# EEZ_DIB_AFE3_r1B3.net
KiCad netlist of a schematic drawn in EAGLE
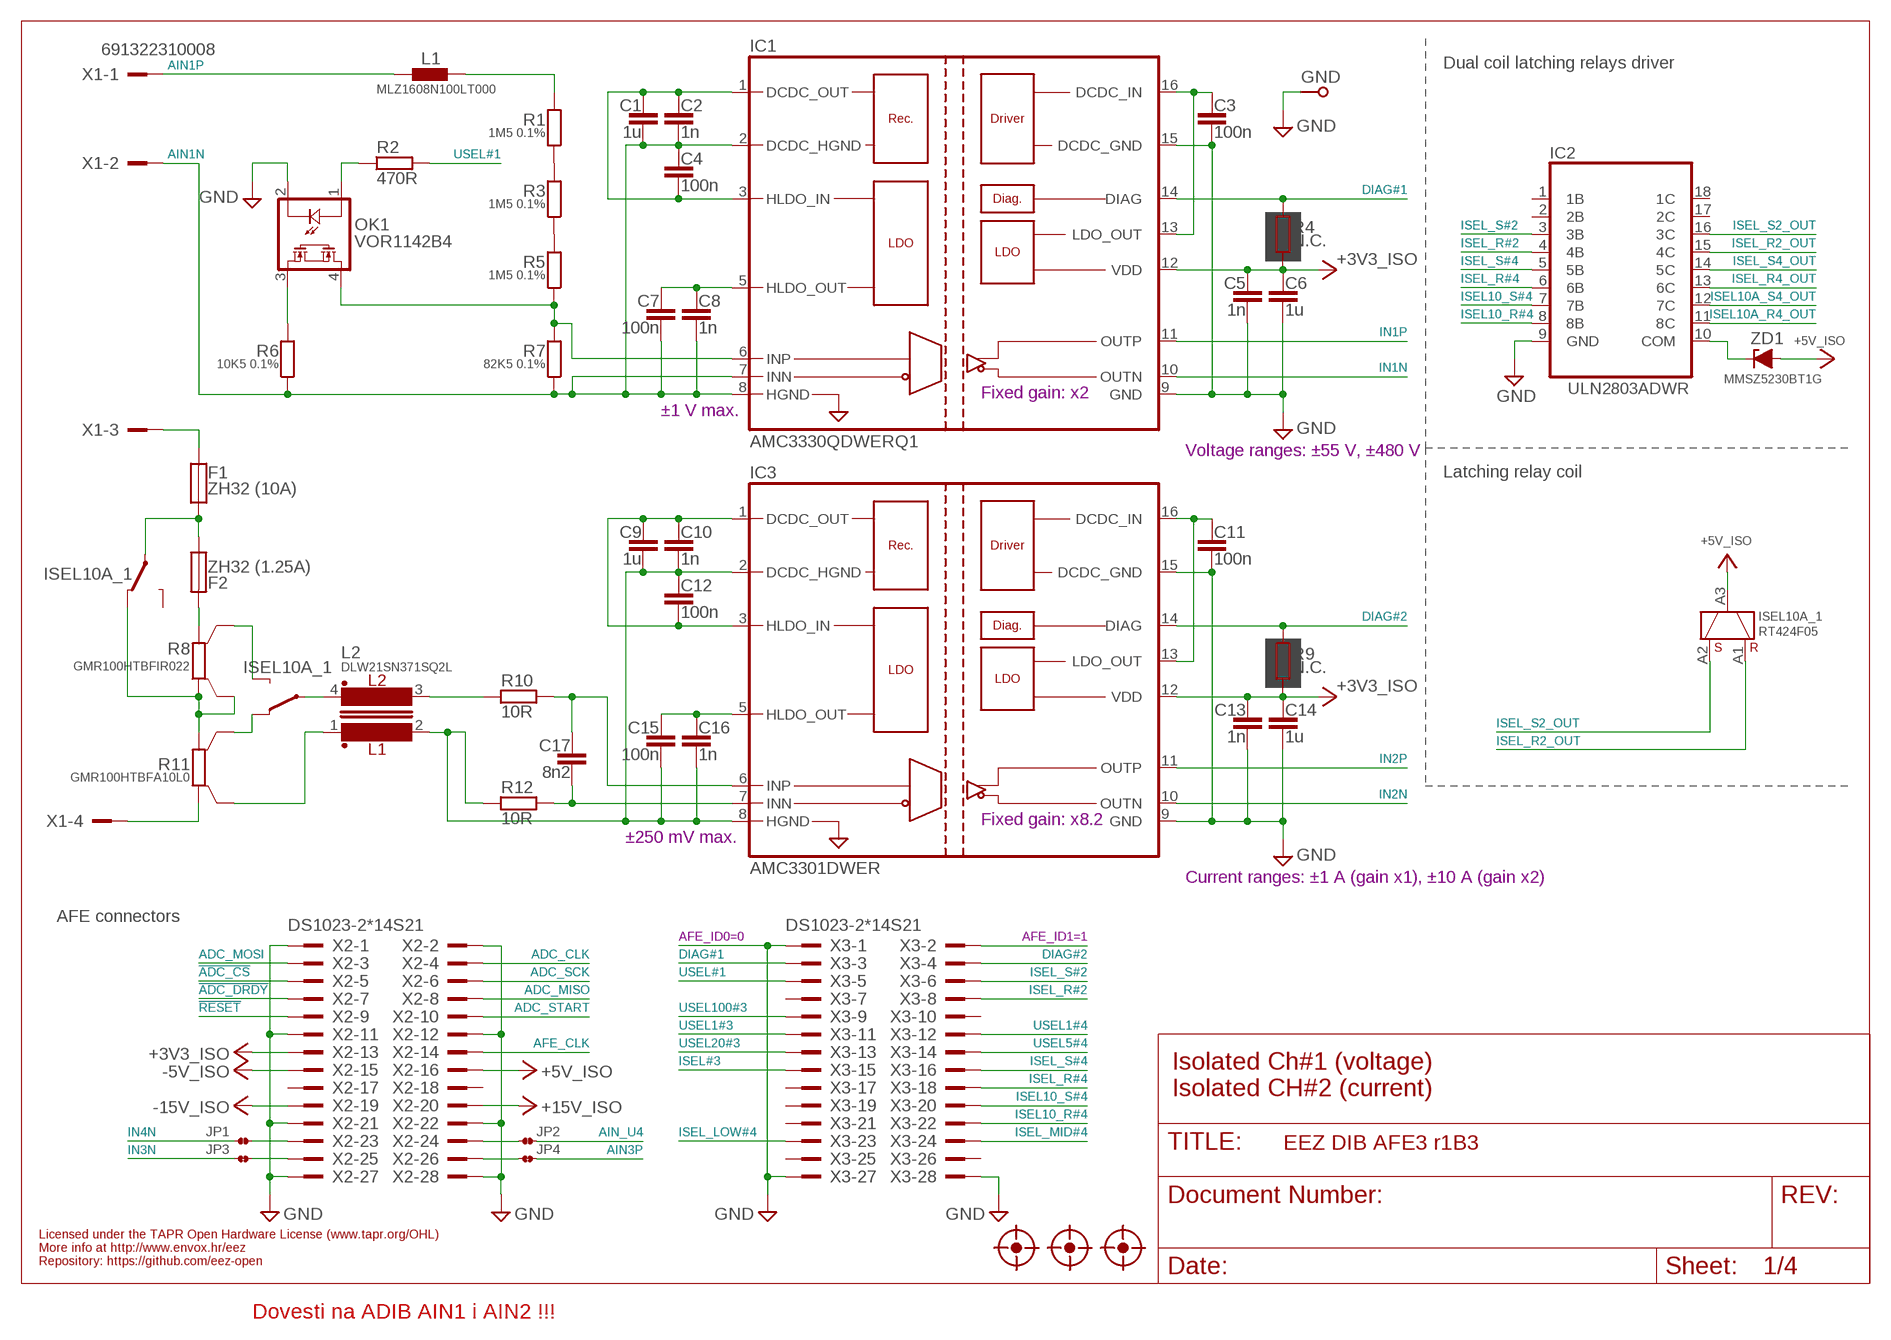
[diagram p0: schematic, sheet 1]
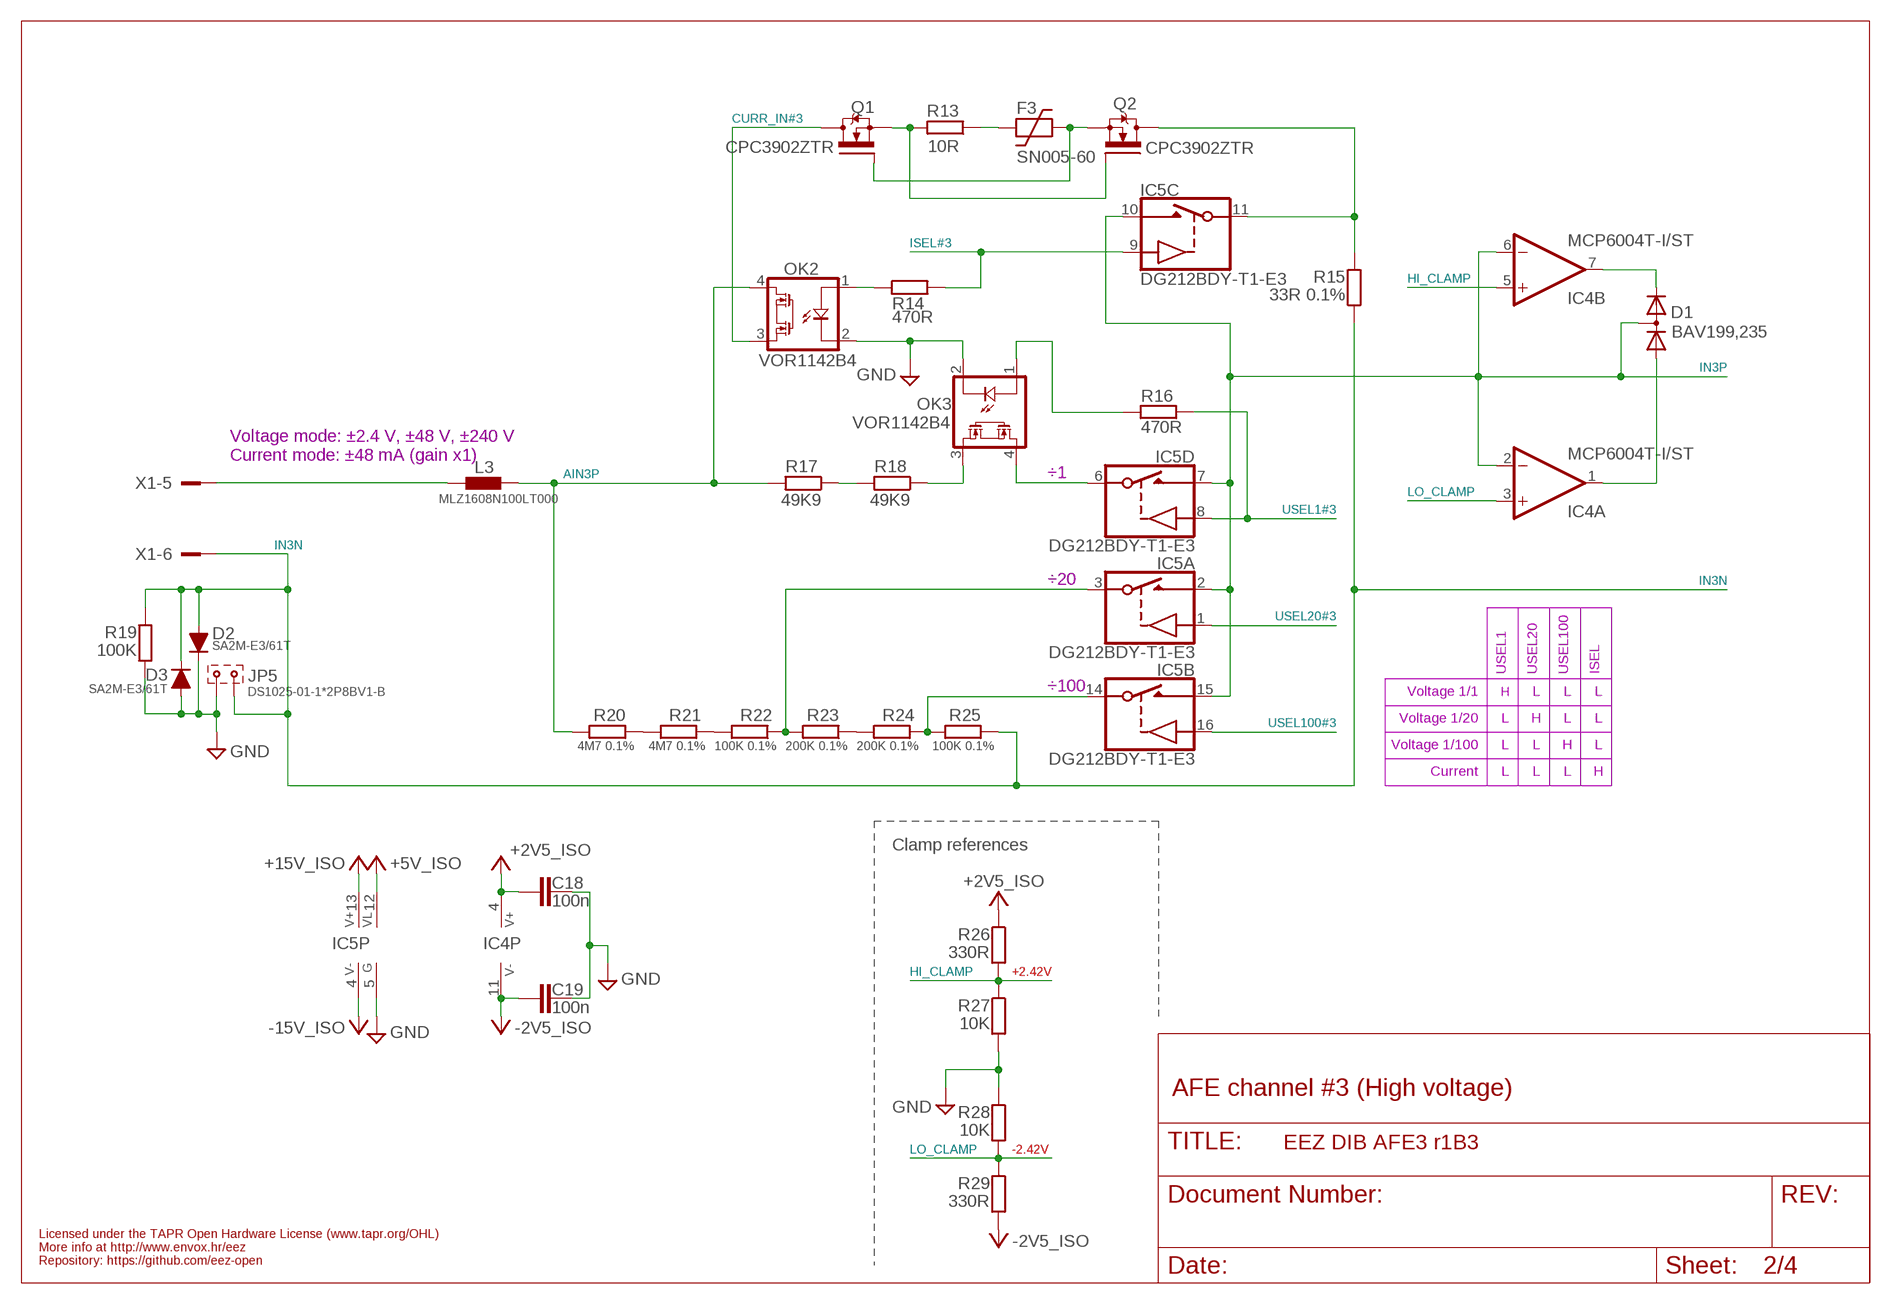
[diagram p1: schematic, sheet 2]
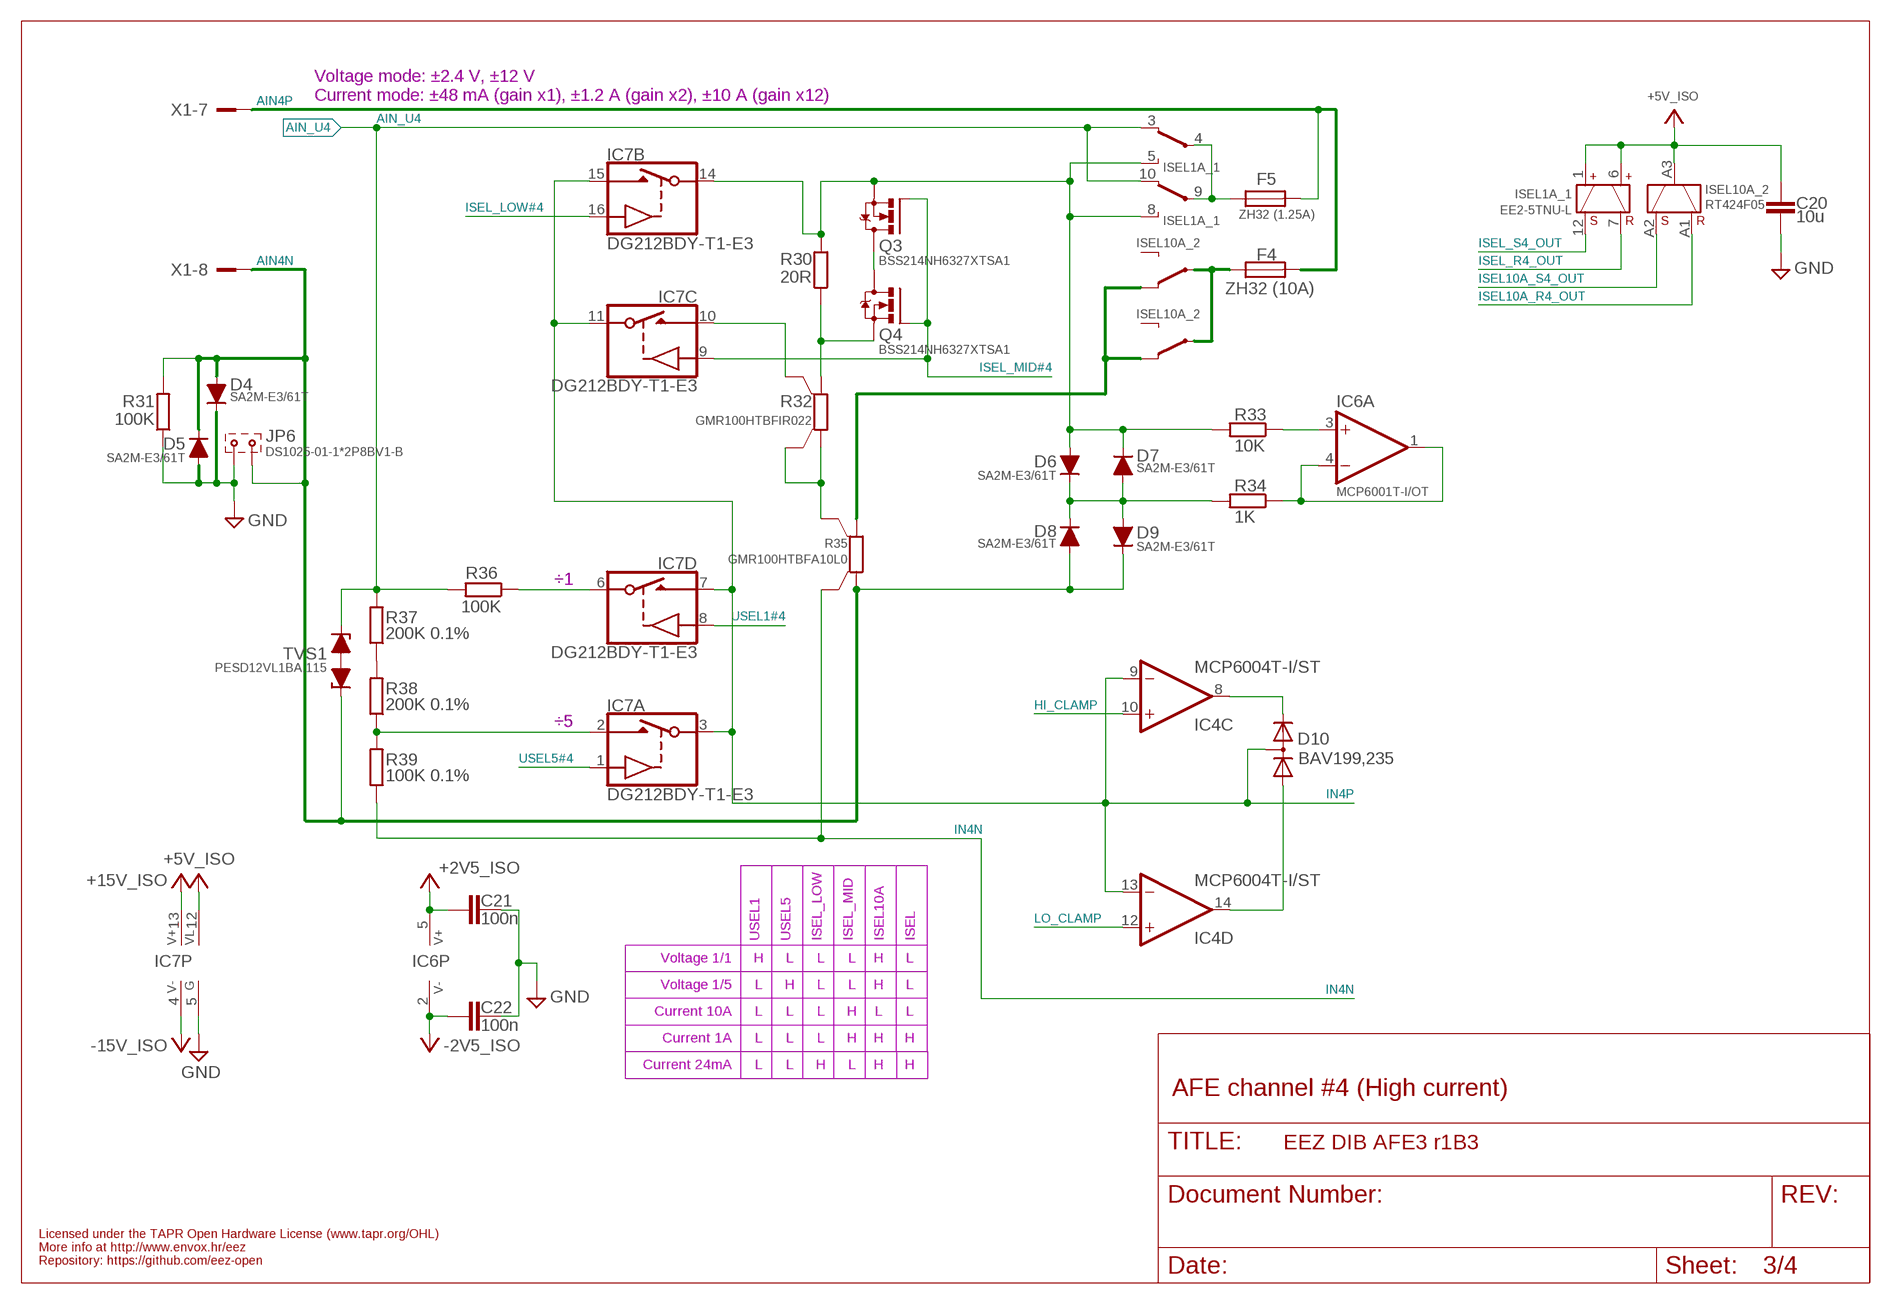
[diagram p2: schematic, sheet 3]
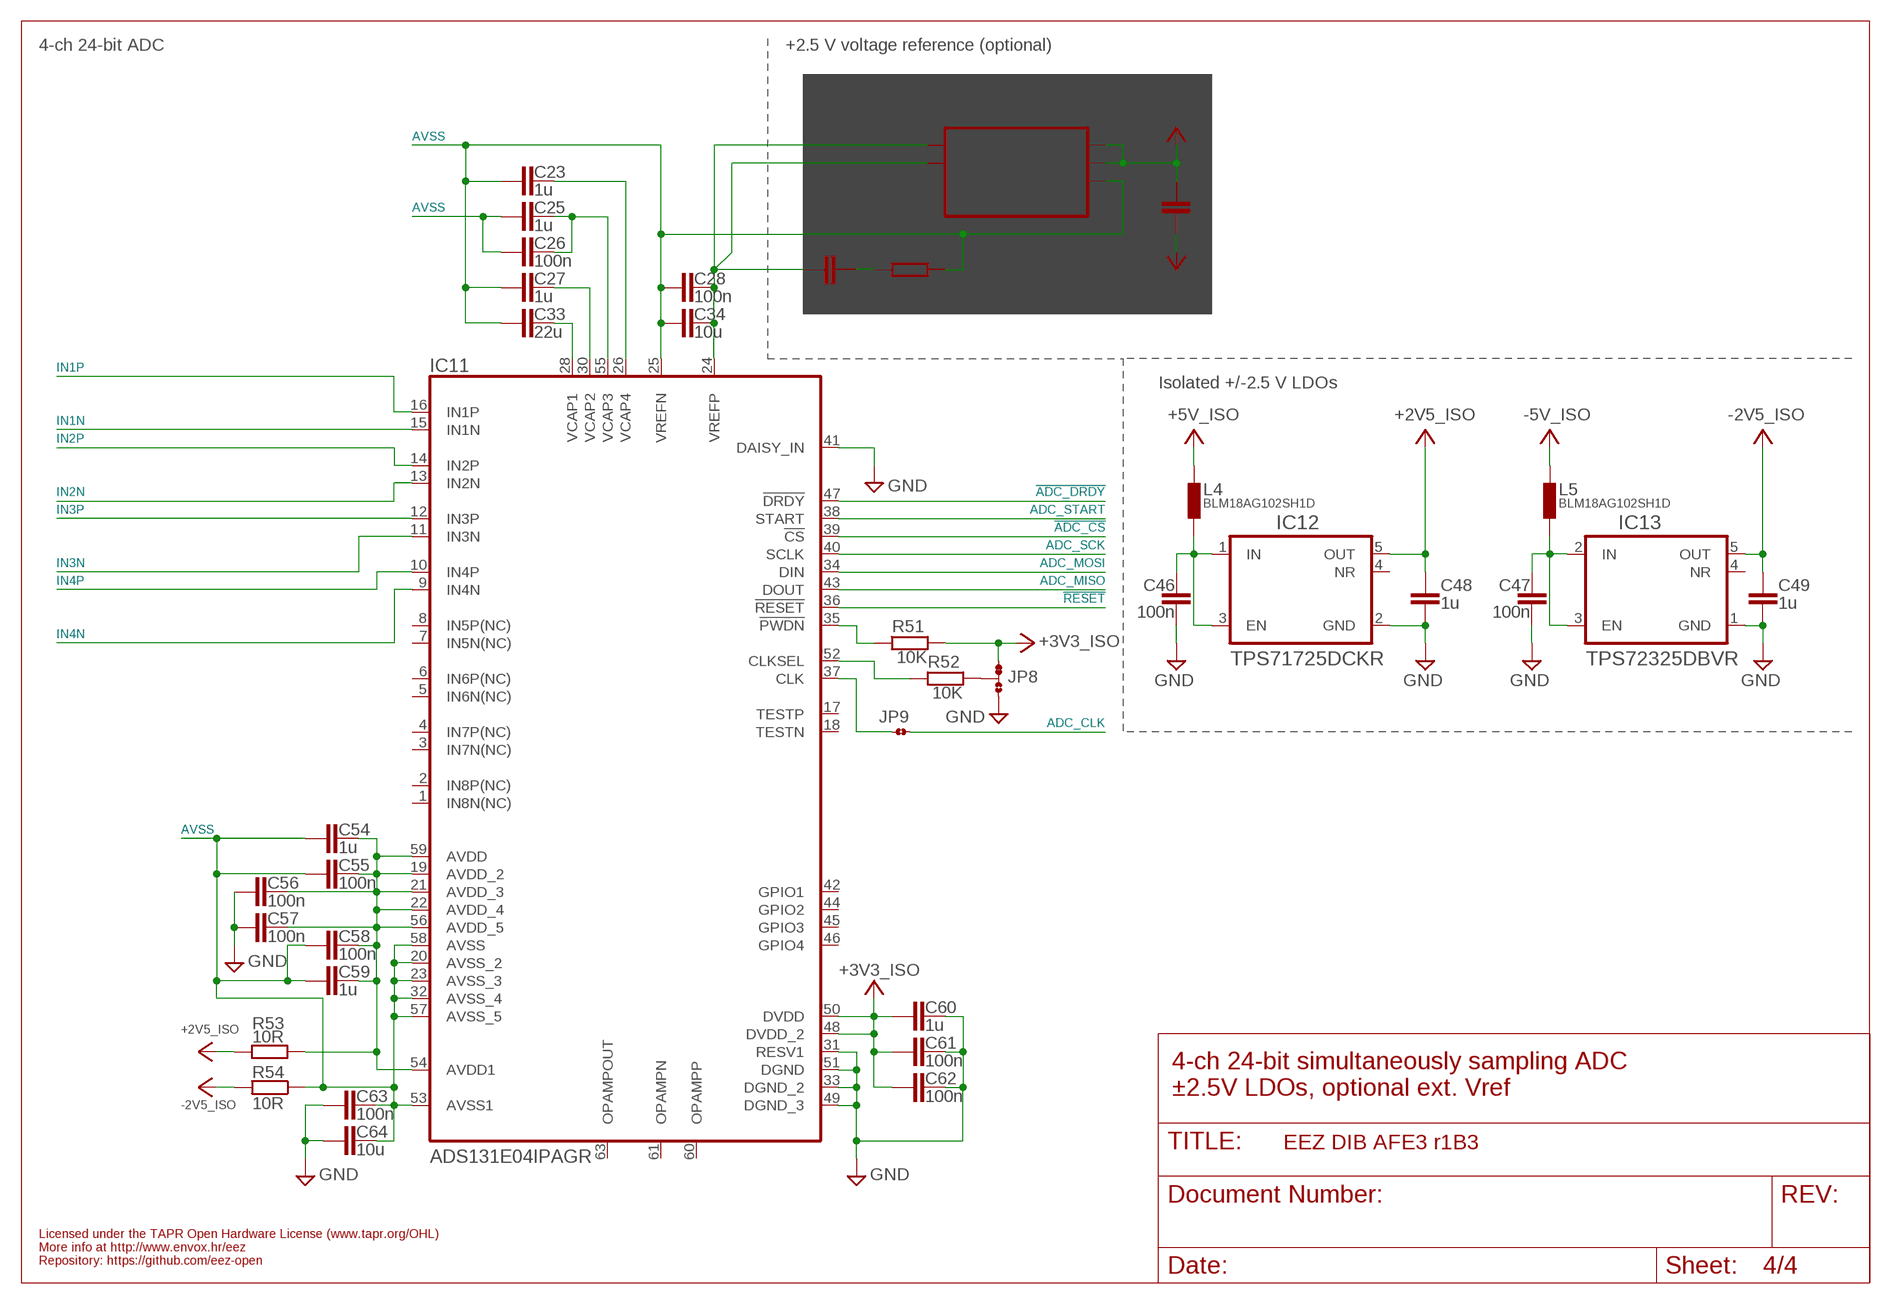
[diagram p3: schematic, sheet 4]

(export (version "E")
  (design (tool "Eeschema 10.0.6"))
  (components
    (comp (ref "C23")
      (value "1u")
      (footprint "eagle-import:C0805")
      (libsource (lib "eagle-import") (part "C-EUC0805"))
    )
    (comp (ref "C24")
      (value "N.C.")
      (footprint "eagle-import:C1206")
      (libsource (lib "eagle-import") (part "C-EUC1206"))
    )
    (comp (ref "C25")
      (value "1u")
      (footprint "eagle-import:C0805")
      (libsource (lib "eagle-import") (part "C-EUC0805"))
    )
    (comp (ref "C26")
      (value "100n")
      (footprint "eagle-import:C0603")
      (libsource (lib "eagle-import") (part "C-EUC0603"))
    )
    (comp (ref "C27")
      (value "1u")
      (footprint "eagle-import:C0805")
      (libsource (lib "eagle-import") (part "C-EUC0805"))
    )
    (comp (ref "C28")
      (value "100n")
      (footprint "eagle-import:C0603")
      (libsource (lib "eagle-import") (part "C-EUC0603"))
    )
    (comp (ref "C33")
      (value "22u")
      (footprint "eagle-import:C1206")
      (libsource (lib "eagle-import") (part "C-EUC1206"))
    )
    (comp (ref "C34")
      (value "10u")
      (footprint "eagle-import:C1206")
      (libsource (lib "eagle-import") (part "C-EUC1206"))
    )
    (comp (ref "C35")
      (value "N.C.")
      (footprint "eagle-import:C1206")
      (libsource (lib "eagle-import") (part "C-EUC1206"))
    )
    (comp (ref "C46")
      (value "100n")
      (footprint "eagle-import:C0603")
      (libsource (lib "eagle-import") (part "C-EUC0603"))
    )
    (comp (ref "C47")
      (value "100n")
      (footprint "eagle-import:C0603")
      (libsource (lib "eagle-import") (part "C-EUC0603"))
    )
    (comp (ref "C48")
      (value "1u")
      (footprint "eagle-import:C0805")
      (libsource (lib "eagle-import") (part "C-EUC0805"))
    )
    (comp (ref "C49")
      (value "1u")
      (footprint "eagle-import:C0805")
      (libsource (lib "eagle-import") (part "C-EUC0805"))
    )
    (comp (ref "C54")
      (value "1u")
      (footprint "eagle-import:C0805")
      (libsource (lib "eagle-import") (part "C-EUC0805"))
    )
    (comp (ref "C55")
      (value "100n")
      (footprint "eagle-import:C0603")
      (libsource (lib "eagle-import") (part "C-EUC0603"))
    )
    (comp (ref "C56")
      (value "100n")
      (footprint "eagle-import:C0603")
      (libsource (lib "eagle-import") (part "C-EUC0603"))
    )
    (comp (ref "C57")
      (value "100n")
      (footprint "eagle-import:C0603")
      (libsource (lib "eagle-import") (part "C-EUC0603"))
    )
    (comp (ref "C58")
      (value "100n")
      (footprint "eagle-import:C0603")
      (libsource (lib "eagle-import") (part "C-EUC0603"))
    )
    (comp (ref "C59")
      (value "1u")
      (footprint "eagle-import:C0805")
      (libsource (lib "eagle-import") (part "C-EUC0805"))
    )
    (comp (ref "C60")
      (value "1u")
      (footprint "eagle-import:C0805")
      (libsource (lib "eagle-import") (part "C-EUC0805"))
    )
    (comp (ref "C61")
      (value "100n")
      (footprint "eagle-import:C0603")
      (libsource (lib "eagle-import") (part "C-EUC0603"))
    )
    (comp (ref "C62")
      (value "100n")
      (footprint "eagle-import:C0603")
      (libsource (lib "eagle-import") (part "C-EUC0603"))
    )
    (comp (ref "C63")
      (value "100n")
      (footprint "eagle-import:C0603")
      (libsource (lib "eagle-import") (part "C-EUC0603"))
    )
    (comp (ref "C64")
      (value "10u")
      (footprint "eagle-import:C1206")
      (libsource (lib "eagle-import") (part "C-EUC1206"))
    )
    (comp (ref "IC8")
      (value "N.C.")
      (footprint "eagle-import:MSOP-8_MS_LIT")
      (libsource (lib "eagle-import") (part "LTC6655BHMS8"))
    )
    (comp (ref "IC11")
      (value "ADS131E04IPAGR")
      (footprint "eagle-import:PAG64")
      (libsource (lib "eagle-import") (part "ADS131E0XIPAG"))
    )
    (comp (ref "IC12")
      (value "TPS71725DCKR")
      (footprint "eagle-import:DCK5")
      (libsource (lib "eagle-import") (part "TPS71725DCKR"))
    )
    (comp (ref "IC13")
      (value "TPS72325DBVR")
      (footprint "eagle-import:DBV5")
      (libsource (lib "eagle-import") (part "TPS72325DBVR"))
    )
    (comp (ref "JP8")
      (value "JP3-CUT-0805-ROTATED")
      (footprint "eagle-import:JP3-0805-CUT2")
      (libsource (lib "eagle-import") (part "JP3-CUT-0805-ROTATED"))
    )
    (comp (ref "JP9")
      (value "JP2-CUT-0805")
      (footprint "eagle-import:R_0805")
      (libsource (lib "eagle-import") (part "JP2-CUT-0805"))
    )
    (comp (ref "L4")
      (value "BLM18AG102SH1D")
      (footprint "eagle-import:BEAD0603")
      (libsource (lib "eagle-import") (part "FERRITE_BEAD0603"))
    )
    (comp (ref "L5")
      (value "BLM18AG102SH1D")
      (footprint "eagle-import:BEAD0603")
      (libsource (lib "eagle-import") (part "FERRITE_BEAD0603"))
    )
    (comp (ref "R51")
      (value "10K")
      (footprint "eagle-import:R0805")
      (libsource (lib "eagle-import") (part "R-EU_R0805"))
    )
    (comp (ref "R52")
      (value "10K")
      (footprint "eagle-import:R0805")
      (libsource (lib "eagle-import") (part "R-EU_R0805"))
    )
    (comp (ref "R53")
      (value "10R")
      (footprint "eagle-import:R0805")
      (libsource (lib "eagle-import") (part "R-EU_R0805"))
    )
    (comp (ref "R54")
      (value "10R")
      (footprint "eagle-import:R0805")
      (libsource (lib "eagle-import") (part "R-EU_R0805"))
    )
    (comp (ref "R65")
      (value "N.C.")
      (footprint "eagle-import:R0805")
      (libsource (lib "eagle-import") (part "R-EU_R0805"))
    )
    (comp (ref "C18")
      (value "100n")
      (footprint "eagle-import:C0603")
      (libsource (lib "eagle-import") (part "C-EUC0603"))
    )
    (comp (ref "C19")
      (value "100n")
      (footprint "eagle-import:C0603")
      (libsource (lib "eagle-import") (part "C-EUC0603"))
    )
    (comp (ref "D1")
      (value "BAV199,235")
      (footprint "eagle-import:SOT23")
      (libsource (lib "eagle-import") (part "BAV199"))
    )
    (comp (ref "D2")
      (value "SA2M-E3/61T")
      (footprint "eagle-import:SMA_NARROW")
      (libsource (lib "eagle-import") (part "DIODE_SMA-NARROW"))
    )
    (comp (ref "D3")
      (value "SA2M-E3/61T")
      (footprint "eagle-import:SMA_NARROW")
      (libsource (lib "eagle-import") (part "DIODE_SMA-NARROW"))
    )
    (comp (ref "F3")
      (value "SN005-60")
      (footprint "eagle-import:C1206-HV")
      (libsource (lib "eagle-import") (part "FUSE_RESETTABLE2"))
    )
    (comp (ref "IC4")
      (value "MCP6004T-I/ST")
      (footprint "eagle-import:PW(R-PDSO-G14)")
      (libsource (lib "eagle-import") (part "OPA4197PW"))
    )
    (comp (ref "IC5")
      (value "DG212BDY-T1-E3")
      (footprint "eagle-import:SO16")
      (libsource (lib "eagle-import") (part "DG212BDY-T1-E3"))
    )
    (comp (ref "JP5")
      (value "DS1025-01-1*2P8BV1-B")
      (footprint "eagle-import:2MM-2")
      (libsource (lib "eagle-import") (part "JUMPER-2PIN-2MM"))
    )
    (comp (ref "L3")
      (value "MLZ1608N100LT000")
      (footprint "eagle-import:BEAD0603")
      (libsource (lib "eagle-import") (part "FERRITE_BEAD0603"))
    )
    (comp (ref "OK2")
      (value "VOR1142B4")
      (footprint "eagle-import:DIL4-SMD")
      (libsource (lib "eagle-import") (part "VOR1142B4"))
    )
    (comp (ref "OK3")
      (value "VOR1142B4")
      (footprint "eagle-import:DIL4-SMD")
      (libsource (lib "eagle-import") (part "VOR1142B4"))
    )
    (comp (ref "Q1")
      (value "CPC3902ZTR")
      (footprint "eagle-import:SOT230P700X180-4N")
      (libsource (lib "eagle-import") (part "BSP129SOT-223"))
    )
    (comp (ref "Q2")
      (value "CPC3902ZTR")
      (footprint "eagle-import:SOT230P700X180-4N")
      (libsource (lib "eagle-import") (part "BSP129SOT-223"))
    )
    (comp (ref "R13")
      (value "10R")
      (footprint "eagle-import:R0805")
      (libsource (lib "eagle-import") (part "R-EU_R0805"))
    )
    (comp (ref "R14")
      (value "470R")
      (footprint "eagle-import:R0805")
      (libsource (lib "eagle-import") (part "R-EU_R0805"))
    )
    (comp (ref "R15")
      (value "33R 0.1%")
      (footprint "eagle-import:R1206")
      (libsource (lib "eagle-import") (part "R-EU_R1206"))
    )
    (comp (ref "R16")
      (value "470R")
      (footprint "eagle-import:R0805")
      (libsource (lib "eagle-import") (part "R-EU_R0805"))
    )
    (comp (ref "R17")
      (value "49K9")
      (footprint "eagle-import:R1206")
      (libsource (lib "eagle-import") (part "R-EU_R1206"))
    )
    (comp (ref "R18")
      (value "49K9")
      (footprint "eagle-import:R1206")
      (libsource (lib "eagle-import") (part "R-EU_R1206"))
    )
    (comp (ref "R19")
      (value "100K")
      (footprint "eagle-import:R1206")
      (libsource (lib "eagle-import") (part "R-EU_R1206"))
    )
    (comp (ref "R20")
      (value "4M7 0.1%")
      (footprint "eagle-import:R1206")
      (libsource (lib "eagle-import") (part "R-EU_R1206"))
    )
    (comp (ref "R21")
      (value "4M7 0.1%")
      (footprint "eagle-import:R1206")
      (libsource (lib "eagle-import") (part "R-EU_R1206"))
    )
    (comp (ref "R22")
      (value "100K 0.1%")
      (footprint "eagle-import:R1206")
      (libsource (lib "eagle-import") (part "R-EU_R1206"))
    )
    (comp (ref "R23")
      (value "200K 0.1%")
      (footprint "eagle-import:R1206")
      (libsource (lib "eagle-import") (part "R-EU_R1206"))
    )
    (comp (ref "R24")
      (value "200K 0.1%")
      (footprint "eagle-import:R1206")
      (libsource (lib "eagle-import") (part "R-EU_R1206"))
    )
    (comp (ref "R25")
      (value "100K 0.1%")
      (footprint "eagle-import:R1206")
      (libsource (lib "eagle-import") (part "R-EU_R1206"))
    )
    (comp (ref "R26")
      (value "330R")
      (footprint "eagle-import:R0805")
      (libsource (lib "eagle-import") (part "R-EU_R0805"))
    )
    (comp (ref "R27")
      (value "10K")
      (footprint "eagle-import:R0805")
      (libsource (lib "eagle-import") (part "R-EU_R0805"))
    )
    (comp (ref "R28")
      (value "10K")
      (footprint "eagle-import:R0805")
      (libsource (lib "eagle-import") (part "R-EU_R0805"))
    )
    (comp (ref "R29")
      (value "330R")
      (footprint "eagle-import:R0805")
      (libsource (lib "eagle-import") (part "R-EU_R0805"))
    )
    (comp (ref "X1")
      (value "691322310008")
      (footprint "eagle-import:691322310008")
      (libsource (lib "eagle-import") (part "691322310008"))
    )
    (comp (ref "C20")
      (value "10u")
      (footprint "eagle-import:C1206")
      (libsource (lib "eagle-import") (part "C-EUC1206"))
    )
    (comp (ref "C21")
      (value "100n")
      (footprint "eagle-import:C0603")
      (libsource (lib "eagle-import") (part "C-EUC0603"))
    )
    (comp (ref "C22")
      (value "100n")
      (footprint "eagle-import:C0603")
      (libsource (lib "eagle-import") (part "C-EUC0603"))
    )
    (comp (ref "D4")
      (value "SA2M-E3/61T")
      (footprint "eagle-import:SMA_NARROW")
      (libsource (lib "eagle-import") (part "DIODE_SMA-NARROW"))
    )
    (comp (ref "D5")
      (value "SA2M-E3/61T")
      (footprint "eagle-import:SMA_NARROW")
      (libsource (lib "eagle-import") (part "DIODE_SMA-NARROW"))
    )
    (comp (ref "D6")
      (value "SA2M-E3/61T")
      (footprint "eagle-import:SMA_NARROW")
      (libsource (lib "eagle-import") (part "DIODE_SMA-NARROW"))
    )
    (comp (ref "D7")
      (value "SA2M-E3/61T")
      (footprint "eagle-import:SMA_NARROW")
      (libsource (lib "eagle-import") (part "DIODE_SMA-NARROW"))
    )
    (comp (ref "D8")
      (value "SA2M-E3/61T")
      (footprint "eagle-import:SMA_NARROW")
      (libsource (lib "eagle-import") (part "DIODE_SMA-NARROW"))
    )
    (comp (ref "D9")
      (value "SA2M-E3/61T")
      (footprint "eagle-import:SMA_NARROW")
      (libsource (lib "eagle-import") (part "DIODE_SMA-NARROW"))
    )
    (comp (ref "D10")
      (value "BAV199,235")
      (footprint "eagle-import:SOT23")
      (libsource (lib "eagle-import") (part "BAV199"))
    )
    (comp (ref "F4")
      (value "ZH32 (10A)")
      (footprint "eagle-import:ZH32")
      (libsource (lib "eagle-import") (part "ZH32"))
    )
    (comp (ref "F5")
      (value "ZH32 (1.25A)")
      (footprint "eagle-import:ZH32")
      (libsource (lib "eagle-import") (part "ZH32"))
    )
    (comp (ref "IC6")
      (value "MCP6001T-I/OT")
      (footprint "eagle-import:DBV5")
      (libsource (lib "eagle-import") (part "OPA376AIDBVR"))
    )
    (comp (ref "IC7")
      (value "DG212BDY-T1-E3")
      (footprint "eagle-import:SO16")
      (libsource (lib "eagle-import") (part "DG212BDY-T1-E3"))
    )
    (comp (ref "ISEL1A_1")
      (value "EE2-5TNU-L")
      (footprint "eagle-import:G6SK-2F")
      (libsource (lib "eagle-import") (part "G6SK-2F"))
    )
    (comp (ref "ISEL10A_2")
      (value "RT424F05")
      (footprint "eagle-import:RT424FXX")
      (libsource (lib "eagle-import") (part "RT424FXX"))
    )
    (comp (ref "JP6")
      (value "DS1025-01-1*2P8BV1-B")
      (footprint "eagle-import:2MM-2")
      (libsource (lib "eagle-import") (part "JUMPER-2PIN-2MM"))
    )
    (comp (ref "Q3")
      (value "BSS214NH6327XTSA1")
      (footprint "eagle-import:SOT103P240X110-3N")
      (fields
        (field (name "MPN") "2N7002-7-F")
        (field (name "MPN_1") "2N7002-7-F")
        (field (name "OC_FARNELL") "1713823")
        (field (name "OC_NEWARK") "25R5679")
        (field (name "PACKAGE") "SOT-23-3")
        (field (name "SUPPLIER") "DIODES INC.")
      )
      (libsource (lib "eagle-import") (part "2N7002"))
    )
    (comp (ref "Q4")
      (value "BSS214NH6327XTSA1")
      (footprint "eagle-import:SOT103P240X110-3N")
      (fields (field (name "MPN") "2N7002-7-F"))
      (libsource (lib "eagle-import") (part "2N7002"))
    )
    (comp (ref "R30")
      (value "20R")
      (footprint "eagle-import:R1206")
      (libsource (lib "eagle-import") (part "R-EU_R1206"))
    )
    (comp (ref "R31")
      (value "100K")
      (footprint "eagle-import:R1206")
      (libsource (lib "eagle-import") (part "R-EU_R1206"))
    )
    (comp (ref "R32")
      (value "GMR100HTBFIR022")
      (footprint "eagle-import:R_2512-4WIRE")
      (libsource (lib "eagle-import") (part "R-EU_4WIRE2512"))
    )
    (comp (ref "R33")
      (value "10K")
      (footprint "eagle-import:R0805")
      (libsource (lib "eagle-import") (part "R-EU_R0805"))
    )
    (comp (ref "R34")
      (value "1K")
      (footprint "eagle-import:R0805")
      (libsource (lib "eagle-import") (part "R-EU_R0805"))
    )
    (comp (ref "R35")
      (value "GMR100HTBFA10L0")
      (footprint "eagle-import:R_2512-4WIRE")
      (libsource (lib "eagle-import") (part "R-EU_4WIRE2512"))
    )
    (comp (ref "R36")
      (value "100K")
      (footprint "eagle-import:R1206")
      (libsource (lib "eagle-import") (part "R-EU_R1206"))
    )
    (comp (ref "R37")
      (value "200K 0.1%")
      (footprint "eagle-import:R1206")
      (libsource (lib "eagle-import") (part "R-EU_R1206"))
    )
    (comp (ref "R38")
      (value "200K 0.1%")
      (footprint "eagle-import:R1206")
      (libsource (lib "eagle-import") (part "R-EU_R1206"))
    )
    (comp (ref "R39")
      (value "100K 0.1%")
      (footprint "eagle-import:R1206")
      (libsource (lib "eagle-import") (part "R-EU_R1206"))
    )
    (comp (ref "TVS1")
      (value "PESD12VL1BA,115")
      (footprint "eagle-import:SOD323-BIDIR")
      (libsource (lib "eagle-import") (part "PESDXL1BA"))
    )
    (comp (ref "C1")
      (value "1u")
      (footprint "eagle-import:C0603")
      (libsource (lib "eagle-import") (part "C-EUC0603"))
    )
    (comp (ref "C2")
      (value "1n")
      (footprint "eagle-import:C0603")
      (libsource (lib "eagle-import") (part "C-EUC0603"))
    )
    (comp (ref "C3")
      (value "100n")
      (footprint "eagle-import:C0603")
      (libsource (lib "eagle-import") (part "C-EUC0603"))
    )
    (comp (ref "C4")
      (value "100n")
      (footprint "eagle-import:C0603")
      (libsource (lib "eagle-import") (part "C-EUC0603"))
    )
    (comp (ref "C5")
      (value "1n")
      (footprint "eagle-import:C1206")
      (libsource (lib "eagle-import") (part "C-EUC1206"))
    )
    (comp (ref "C6")
      (value "1u")
      (footprint "eagle-import:C1206")
      (libsource (lib "eagle-import") (part "C-EUC1206"))
    )
    (comp (ref "C7")
      (value "100n")
      (footprint "eagle-import:C1206")
      (libsource (lib "eagle-import") (part "C-EUC1206"))
    )
    (comp (ref "C8")
      (value "1n")
      (footprint "eagle-import:C1206")
      (libsource (lib "eagle-import") (part "C-EUC1206"))
    )
    (comp (ref "C9")
      (value "1u")
      (footprint "eagle-import:C0603")
      (libsource (lib "eagle-import") (part "C-EUC0603"))
    )
    (comp (ref "C10")
      (value "1n")
      (footprint "eagle-import:C0603")
      (libsource (lib "eagle-import") (part "C-EUC0603"))
    )
    (comp (ref "C11")
      (value "100n")
      (footprint "eagle-import:C0603")
      (libsource (lib "eagle-import") (part "C-EUC0603"))
    )
    (comp (ref "C12")
      (value "100n")
      (footprint "eagle-import:C0603")
      (libsource (lib "eagle-import") (part "C-EUC0603"))
    )
    (comp (ref "C13")
      (value "1n")
      (footprint "eagle-import:C1206")
      (libsource (lib "eagle-import") (part "C-EUC1206"))
    )
    (comp (ref "C14")
      (value "1u")
      (footprint "eagle-import:C1206")
      (libsource (lib "eagle-import") (part "C-EUC1206"))
    )
    (comp (ref "C15")
      (value "100n")
      (footprint "eagle-import:C1206")
      (libsource (lib "eagle-import") (part "C-EUC1206"))
    )
    (comp (ref "C16")
      (value "1n")
      (footprint "eagle-import:C1206")
      (libsource (lib "eagle-import") (part "C-EUC1206"))
    )
    (comp (ref "C17")
      (value "8n2")
      (footprint "eagle-import:C0603")
      (libsource (lib "eagle-import") (part "C-EUC0603"))
    )
    (comp (ref "F1")
      (value "ZH32 (10A)")
      (footprint "eagle-import:ZH32")
      (libsource (lib "eagle-import") (part "ZH32"))
    )
    (comp (ref "F2")
      (value "ZH32 (1.25A)")
      (footprint "eagle-import:ZH32")
      (libsource (lib "eagle-import") (part "ZH32"))
    )
    (comp (ref "FM1")
      (value "FIDUCIAL_2")
      (footprint "eagle-import:FIDUCIAL_DUAL")
      (libsource (lib "eagle-import") (part "FIDUCIAL_2"))
    )
    (comp (ref "FM2")
      (value "FIDUCIAL_2")
      (footprint "eagle-import:FIDUCIAL_DUAL")
      (libsource (lib "eagle-import") (part "FIDUCIAL_2"))
    )
    (comp (ref "FM3")
      (value "FIDUCIAL_2")
      (footprint "eagle-import:FIDUCIAL_DUAL")
      (libsource (lib "eagle-import") (part "FIDUCIAL_2"))
    )
    (comp (ref "GND")
      (value "PCB_TEST_TABSHIELD")
      (footprint "eagle-import:PCB_SHIELD_TAB")
      (libsource (lib "eagle-import") (part "PCB_TEST_TABSHIELD"))
    )
    (comp (ref "IC1")
      (value "AMC3330QDWERQ1")
      (footprint "eagle-import:DW16")
      (libsource (lib "eagle-import") (part "AMC3301DWER"))
    )
    (comp (ref "IC2")
      (value "ULN2803ADWR")
      (footprint "eagle-import:DW18_TEX-M")
      (libsource (lib "eagle-import") (part "ULN2803ADWR"))
    )
    (comp (ref "IC3")
      (value "AMC3301DWER")
      (footprint "eagle-import:DW16")
      (libsource (lib "eagle-import") (part "AMC3301DWER"))
    )
    (comp (ref "ISEL10A_1")
      (value "RT424F05")
      (footprint "eagle-import:RT424FXX")
      (libsource (lib "eagle-import") (part "RT424FXX"))
    )
    (comp (ref "JP1")
      (value "JP2-NOCUT-0805")
      (footprint "eagle-import:JP2-0805-NOCUT")
      (libsource (lib "eagle-import") (part "JP2-NOCUT-0805"))
    )
    (comp (ref "JP2")
      (value "JP2-NOCUT-0805")
      (footprint "eagle-import:JP2-0805-NOCUT")
      (libsource (lib "eagle-import") (part "JP2-NOCUT-0805"))
    )
    (comp (ref "JP3")
      (value "JP2-NOCUT-0805")
      (footprint "eagle-import:JP2-0805-NOCUT")
      (libsource (lib "eagle-import") (part "JP2-NOCUT-0805"))
    )
    (comp (ref "JP4")
      (value "JP2-NOCUT-0805")
      (footprint "eagle-import:JP2-0805-NOCUT")
      (libsource (lib "eagle-import") (part "JP2-NOCUT-0805"))
    )
    (comp (ref "L1")
      (value "MLZ1608N100LT000")
      (footprint "eagle-import:BEAD0603")
      (libsource (lib "eagle-import") (part "FERRITE_BEAD0603"))
    )
    (comp (ref "L2")
      (value "DLW21SN371SQ2L")
      (footprint "eagle-import:MURATA_DLW21S")
      (libsource (lib "eagle-import") (part "DLW21S"))
    )
    (comp (ref "OK1")
      (value "VOR1142B4")
      (footprint "eagle-import:DIL4-SMD")
      (libsource (lib "eagle-import") (part "VOR1142B4"))
    )
    (comp (ref "R1")
      (value "1M5 0.1%")
      (footprint "eagle-import:R1206")
      (libsource (lib "eagle-import") (part "R-EU_R1206"))
    )
    (comp (ref "R2")
      (value "470R")
      (footprint "eagle-import:R0805")
      (libsource (lib "eagle-import") (part "R-EU_R0805"))
    )
    (comp (ref "R3")
      (value "1M5 0.1%")
      (footprint "eagle-import:R1206")
      (libsource (lib "eagle-import") (part "R-EU_R1206"))
    )
    (comp (ref "R4")
      (value "N.C.")
      (footprint "eagle-import:R0805")
      (libsource (lib "eagle-import") (part "R-EU_R0805"))
    )
    (comp (ref "R5")
      (value "1M5 0.1%")
      (footprint "eagle-import:R1206")
      (libsource (lib "eagle-import") (part "R-EU_R1206"))
    )
    (comp (ref "R6")
      (value "10K5 0.1%")
      (footprint "eagle-import:R1206")
      (libsource (lib "eagle-import") (part "R-EU_R1206"))
    )
    (comp (ref "R7")
      (value "82K5 0.1%")
      (footprint "eagle-import:R1206")
      (libsource (lib "eagle-import") (part "R-EU_R1206"))
    )
    (comp (ref "R8")
      (value "GMR100HTBFIR022")
      (footprint "eagle-import:R_2512-4WIRE")
      (libsource (lib "eagle-import") (part "R-EU_4WIRE2512"))
    )
    (comp (ref "R9")
      (value "N.C.")
      (footprint "eagle-import:R0805")
      (libsource (lib "eagle-import") (part "R-EU_R0805"))
    )
    (comp (ref "R10")
      (value "10R")
      (footprint "eagle-import:R0805")
      (libsource (lib "eagle-import") (part "R-EU_R0805"))
    )
    (comp (ref "R11")
      (value "GMR100HTBFA10L0")
      (footprint "eagle-import:R_2512-4WIRE")
      (libsource (lib "eagle-import") (part "R-EU_4WIRE2512"))
    )
    (comp (ref "R12")
      (value "10R")
      (footprint "eagle-import:R0805")
      (libsource (lib "eagle-import") (part "R-EU_R0805"))
    )
    (comp (ref "X2")
      (value "DS1023-2*14S21")
      (footprint "eagle-import:TSW-114-07-F-D")
      (libsource (lib "eagle-import") (part "TSW-114-07-F-D"))
    )
    (comp (ref "X3")
      (value "DS1023-2*14S21")
      (footprint "eagle-import:TSW-114-07-F-D")
      (libsource (lib "eagle-import") (part "TSW-114-07-F-D"))
    )
    (comp (ref "ZD1")
      (value "MMSZ5230BT1G")
      (footprint "eagle-import:SOD123")
      (libsource (lib "eagle-import") (part "ZENER-DIODESOD123"))
    )
  )
  (nets
    (net (code "1") (name "+2V5_ISO") (class "Default")
      (node (ref "C18") (pin "2") (pinfunction "2_2") (pintype "passive"))
      (node (ref "C21") (pin "2") (pinfunction "2_2") (pintype "passive"))
      (node (ref "C48") (pin "2") (pinfunction "2_2") (pintype "passive"))
      (node (ref "IC12") (pin "5") (pinfunction "OUT_5") (pintype "passive"))
      (node (ref "IC4") (pin "4") (pinfunction "V+_4") (pintype "power_in"))
      (node (ref "IC6") (pin "5") (pinfunction "V+_5") (pintype "power_in"))
      (node (ref "R26") (pin "1") (pinfunction "1_1") (pintype "passive"))
      (node (ref "R53") (pin "1") (pinfunction "1_1") (pintype "passive"))
    )
    (net (code "2") (name "+3V3_ISO") (class "Default")
      (node (ref "C13") (pin "1") (pinfunction "1_1") (pintype "passive"))
      (node (ref "C14") (pin "1") (pinfunction "1_1") (pintype "passive"))
      (node (ref "C5") (pin "1") (pinfunction "1_1") (pintype "passive"))
      (node (ref "C6") (pin "1") (pinfunction "1_1") (pintype "passive"))
      (node (ref "C60") (pin "1") (pinfunction "1_1") (pintype "passive"))
      (node (ref "C61") (pin "2") (pinfunction "2_2") (pintype "passive"))
      (node (ref "C62") (pin "2") (pinfunction "2_2") (pintype "passive"))
      (node (ref "IC1") (pin "12") (pinfunction "VDD_12") (pintype "passive"))
      (node (ref "IC11") (pin "48") (pinfunction "DVDD_2_48") (pintype "power_in"))
      (node (ref "IC11") (pin "50") (pinfunction "DVDD_50") (pintype "power_in"))
      (node (ref "IC3") (pin "12") (pinfunction "VDD_12") (pintype "passive"))
      (node (ref "JP8") (pin "NC") (pinfunction "NC_NC") (pintype "passive"))
      (node (ref "R4") (pin "2") (pinfunction "2_2") (pintype "passive"))
      (node (ref "R51") (pin "2") (pinfunction "2_2") (pintype "passive"))
      (node (ref "R9") (pin "2") (pinfunction "2_2") (pintype "passive"))
      (node (ref "X2") (pin "13") (pinfunction "1_13") (pintype "passive"))
    )
    (net (code "3") (name "+5V_ISO") (class "Default")
      (node (ref "C20") (pin "1") (pinfunction "1_1") (pintype "passive"))
      (node (ref "C24") (pin "1") (pinfunction "1_1") (pintype "passive"))
      (node (ref "IC5") (pin "12") (pinfunction "VL_12") (pintype "power_in"))
      (node (ref "IC7") (pin "12") (pinfunction "VL_12") (pintype "power_in"))
      (node (ref "IC8") (pin "1") (pinfunction "~{SHDN}_1") (pintype "input"))
      (node (ref "IC8") (pin "2") (pinfunction "VIN_2") (pintype "input"))
      (node (ref "ISEL10A_1") (pin "A3") (pinfunction "COM_A3") (pintype "passive"))
      (node (ref "ISEL10A_2") (pin "A3") (pinfunction "COM_A3") (pintype "passive"))
      (node (ref "ISEL1A_1") (pin "1") (pinfunction "S+_1") (pintype "passive"))
      (node (ref "ISEL1A_1") (pin "6") (pinfunction "R+_6") (pintype "passive"))
      (node (ref "L4") (pin "P$2") (pinfunction "2_P$2") (pintype "passive"))
      (node (ref "X2") (pin "16") (pinfunction "1_16") (pintype "passive"))
      (node (ref "ZD1") (pin "A") (pinfunction "A_A") (pintype "passive"))
    )
    (net (code "4") (name "+15V_ISO") (class "Default")
      (node (ref "IC5") (pin "13") (pinfunction "V+_13") (pintype "power_in"))
      (node (ref "IC7") (pin "13") (pinfunction "V+_13") (pintype "power_in"))
      (node (ref "X2") (pin "20") (pinfunction "1_20") (pintype "passive"))
    )
    (net (code "5") (name "-2V5_ISO") (class "Default")
      (node (ref "C19") (pin "2") (pinfunction "2_2") (pintype "passive"))
      (node (ref "C22") (pin "2") (pinfunction "2_2") (pintype "passive"))
      (node (ref "C24") (pin "2") (pinfunction "2_2") (pintype "passive"))
      (node (ref "C49") (pin "2") (pinfunction "2_2") (pintype "passive"))
      (node (ref "IC13") (pin "5") (pinfunction "OUT_5") (pintype "passive"))
      (node (ref "IC4") (pin "11") (pinfunction "V-_11") (pintype "power_in"))
      (node (ref "IC6") (pin "2") (pinfunction "V-_2") (pintype "power_in"))
      (node (ref "R29") (pin "2") (pinfunction "2_2") (pintype "passive"))
      (node (ref "R54") (pin "2") (pinfunction "2_2") (pintype "passive"))
    )
    (net (code "6") (name "-5V_ISO") (class "Default")
      (node (ref "L5") (pin "P$2") (pinfunction "2_P$2") (pintype "passive"))
      (node (ref "X2") (pin "15") (pinfunction "1_15") (pintype "passive"))
    )
    (net (code "7") (name "-15V_ISO") (class "Default")
      (node (ref "IC5") (pin "4") (pinfunction "V-_4") (pintype "power_in"))
      (node (ref "IC7") (pin "4") (pinfunction "V-_4") (pintype "power_in"))
      (node (ref "X2") (pin "19") (pinfunction "1_19") (pintype "passive"))
    )
    (net (code "8") (name "ADC_CLK") (class "Default")
      (node (ref "JP9") (pin "1") (pinfunction "1_1") (pintype "passive"))
      (node (ref "X2") (pin "4") (pinfunction "1_4") (pintype "passive"))
    )
    (net (code "9") (name "ADC_MISO") (class "Default")
      (node (ref "IC11") (pin "43") (pinfunction "DOUT_43") (pintype "output"))
      (node (ref "X2") (pin "8") (pinfunction "1_8") (pintype "passive"))
    )
    (net (code "10") (name "ADC_MOSI") (class "Default")
      (node (ref "IC11") (pin "34") (pinfunction "DIN_34") (pintype "input"))
      (node (ref "X2") (pin "3") (pinfunction "1_3") (pintype "passive"))
    )
    (net (code "11") (name "ADC_SCK") (class "Default")
      (node (ref "IC11") (pin "40") (pinfunction "SCLK_40") (pintype "input"))
      (node (ref "X2") (pin "6") (pinfunction "1_6") (pintype "passive"))
    )
    (net (code "12") (name "ADC_START") (class "Default")
      (node (ref "IC11") (pin "38") (pinfunction "START_38") (pintype "input"))
      (node (ref "X2") (pin "10") (pinfunction "1_10") (pintype "passive"))
    )
    (net (code "13") (name "AFE_CLK") (class "Default")
      (node (ref "X2") (pin "14") (pinfunction "1_14") (pintype "passive"))
    )
    (net (code "14") (name "AIN1N") (class "Default")
      (node (ref "C1") (pin "2") (pinfunction "2_2") (pintype "passive"))
      (node (ref "C2") (pin "2") (pinfunction "2_2") (pintype "passive"))
      (node (ref "C4") (pin "1") (pinfunction "1_1") (pintype "passive"))
      (node (ref "C7") (pin "2") (pinfunction "2_2") (pintype "passive"))
      (node (ref "C8") (pin "2") (pinfunction "2_2") (pintype "passive"))
      (node (ref "IC1") (pin "2") (pinfunction "DCDC_HGND_2") (pintype "passive"))
      (node (ref "IC1") (pin "7") (pinfunction "INN_7") (pintype "input"))
      (node (ref "IC1") (pin "8") (pinfunction "HGND_8") (pintype "passive"))
      (node (ref "R6") (pin "1") (pinfunction "1_1") (pintype "passive"))
      (node (ref "R7") (pin "1") (pinfunction "1_1") (pintype "passive"))
      (node (ref "X1") (pin "2") (pinfunction "1_2") (pintype "passive"))
    )
    (net (code "15") (name "AIN1P") (class "Default")
      (node (ref "L1") (pin "P$2") (pinfunction "2_P$2") (pintype "passive"))
      (node (ref "X1") (pin "1") (pinfunction "1_1") (pintype "passive"))
    )
    (net (code "16") (name "AIN3P") (class "Default")
      (node (ref "JP4") (pin "2") (pinfunction "2_2") (pintype "passive"))
      (node (ref "L3") (pin "P$1") (pinfunction "1_P$1") (pintype "passive"))
      (node (ref "OK2") (pin "4") (pinfunction "S1_4") (pintype "passive"))
      (node (ref "R17") (pin "2") (pinfunction "2_2") (pintype "passive"))
      (node (ref "R20") (pin "2") (pinfunction "2_2") (pintype "passive"))
    )
    (net (code "17") (name "AIN4N") (class "Default")
      (node (ref "D4") (pin "2") (pinfunction "A_2") (pintype "passive"))
      (node (ref "D5") (pin "1") (pinfunction "C_1") (pintype "passive"))
      (node (ref "D8") (pin "2") (pinfunction "A_2") (pintype "passive"))
      (node (ref "D9") (pin "1") (pinfunction "C_1") (pintype "passive"))
      (node (ref "JP6") (pin "1") (pinfunction "1_1") (pintype "passive"))
      (node (ref "R31") (pin "2") (pinfunction "2_2") (pintype "passive"))
      (node (ref "R35") (pin "1") (pinfunction "1_1") (pintype "passive"))
      (node (ref "TVS1") (pin "C1") (pinfunction "1_C1") (pintype "passive"))
      (node (ref "X1") (pin "8") (pinfunction "1_8") (pintype "passive"))
    )
    (net (code "18") (name "AIN4P") (class "Default")
      (node (ref "F4") (pin "2") (pinfunction "2_2") (pintype "passive"))
      (node (ref "F5") (pin "2") (pinfunction "2_2") (pintype "passive"))
      (node (ref "X1") (pin "7") (pinfunction "1_7") (pintype "passive"))
    )
    (net (code "19") (name "AIN_U4") (class "Default")
      (node (ref "ISEL1A_1") (pin "10") (pinfunction "NC_10") (pintype "passive"))
      (node (ref "ISEL1A_1") (pin "3") (pinfunction "NC_3") (pintype "passive"))
      (node (ref "JP2") (pin "2") (pinfunction "2_2") (pintype "passive"))
      (node (ref "R36") (pin "2") (pinfunction "2_2") (pintype "passive"))
      (node (ref "R37") (pin "2") (pinfunction "2_2") (pintype "passive"))
      (node (ref "TVS1") (pin "C2") (pinfunction "2_C2") (pintype "passive"))
    )
    (net (code "20") (name "AVSS") (class "Default")
      (node (ref "C23") (pin "1") (pinfunction "1_1") (pintype "passive"))
      (node (ref "C25") (pin "1") (pinfunction "1_1") (pintype "passive"))
      (node (ref "C26") (pin "2") (pinfunction "2_2") (pintype "passive"))
      (node (ref "C27") (pin "1") (pinfunction "1_1") (pintype "passive"))
      (node (ref "C28") (pin "2") (pinfunction "2_2") (pintype "passive"))
      (node (ref "C33") (pin "1") (pinfunction "1_1") (pintype "passive"))
      (node (ref "C34") (pin "2") (pinfunction "2_2") (pintype "passive"))
      (node (ref "C54") (pin "1") (pinfunction "1_1") (pintype "passive"))
      (node (ref "C55") (pin "2") (pinfunction "2_2") (pintype "passive"))
      (node (ref "C58") (pin "2") (pinfunction "2_2") (pintype "passive"))
      (node (ref "C59") (pin "1") (pinfunction "1_1") (pintype "passive"))
      (node (ref "C63") (pin "1") (pinfunction "1_1") (pintype "passive"))
      (node (ref "C64") (pin "1") (pinfunction "1_1") (pintype "passive"))
      (node (ref "IC11") (pin "20") (pinfunction "AVSS_2_20") (pintype "power_in"))
      (node (ref "IC11") (pin "23") (pinfunction "AVSS_3_23") (pintype "power_in"))
      (node (ref "IC11") (pin "25") (pinfunction "VREFN_25") (pintype "input"))
      (node (ref "IC11") (pin "32") (pinfunction "AVSS_4_32") (pintype "power_in"))
      (node (ref "IC11") (pin "53") (pinfunction "AVSS1_53") (pintype "power_in"))
      (node (ref "IC11") (pin "57") (pinfunction "AVSS_5_57") (pintype "power_in"))
      (node (ref "IC11") (pin "58") (pinfunction "AVSS_58") (pintype "power_in"))
      (node (ref "IC8") (pin "3") (pinfunction "GND_3") (pintype "power_in"))
      (node (ref "IC8") (pin "4") (pinfunction "GND_4") (pintype "power_in"))
      (node (ref "IC8") (pin "5") (pinfunction "GND_5") (pintype "power_in"))
      (node (ref "IC8") (pin "8") (pinfunction "GND_8") (pintype "power_in"))
      (node (ref "R54") (pin "1") (pinfunction "1_1") (pintype "passive"))
      (node (ref "R65") (pin "2") (pinfunction "2_2") (pintype "passive"))
    )
    (net (code "21") (name "CURR_IN#3") (class "Default")
      (node (ref "OK2") (pin "3") (pinfunction "S2_3") (pintype "passive"))
      (node (ref "Q1") (pin "2") (pinfunction "D_2") (pintype "passive"))
      (node (ref "Q1") (pin "4") (pinfunction "D_4") (pintype "passive"))
    )
    (net (code "22") (name "DIAG#1") (class "Default")
      (node (ref "IC1") (pin "14") (pinfunction "DIAG_14") (pintype "output"))
      (node (ref "R4") (pin "1") (pinfunction "1_1") (pintype "passive"))
      (node (ref "X3") (pin "3") (pinfunction "1_3") (pintype "passive"))
    )
    (net (code "23") (name "DIAG#2") (class "Default")
      (node (ref "IC3") (pin "14") (pinfunction "DIAG_14") (pintype "output"))
      (node (ref "R9") (pin "1") (pinfunction "1_1") (pintype "passive"))
      (node (ref "X3") (pin "4") (pinfunction "1_4") (pintype "passive"))
    )
    (net (code "24") (name "GND") (class "Default")
      (node (ref "C11") (pin "2") (pinfunction "2_2") (pintype "passive"))
      (node (ref "C13") (pin "2") (pinfunction "2_2") (pintype "passive"))
      (node (ref "C14") (pin "2") (pinfunction "2_2") (pintype "passive"))
      (node (ref "C18") (pin "1") (pinfunction "1_1") (pintype "passive"))
      (node (ref "C19") (pin "1") (pinfunction "1_1") (pintype "passive"))
      (node (ref "C20") (pin "2") (pinfunction "2_2") (pintype "passive"))
      (node (ref "C21") (pin "1") (pinfunction "1_1") (pintype "passive"))
      (node (ref "C22") (pin "1") (pinfunction "1_1") (pintype "passive"))
      (node (ref "C3") (pin "2") (pinfunction "2_2") (pintype "passive"))
      (node (ref "C46") (pin "2") (pinfunction "2_2") (pintype "passive"))
      (node (ref "C47") (pin "2") (pinfunction "2_2") (pintype "passive"))
      (node (ref "C48") (pin "1") (pinfunction "1_1") (pintype "passive"))
      (node (ref "C49") (pin "1") (pinfunction "1_1") (pintype "passive"))
      (node (ref "C5") (pin "2") (pinfunction "2_2") (pintype "passive"))
      (node (ref "C56") (pin "2") (pinfunction "2_2") (pintype "passive"))
      (node (ref "C57") (pin "2") (pinfunction "2_2") (pintype "passive"))
      (node (ref "C6") (pin "2") (pinfunction "2_2") (pintype "passive"))
      (node (ref "C60") (pin "2") (pinfunction "2_2") (pintype "passive"))
      (node (ref "C61") (pin "1") (pinfunction "1_1") (pintype "passive"))
      (node (ref "C62") (pin "1") (pinfunction "1_1") (pintype "passive"))
      (node (ref "C63") (pin "2") (pinfunction "2_2") (pintype "passive"))
      (node (ref "C64") (pin "2") (pinfunction "2_2") (pintype "passive"))
      (node (ref "D2") (pin "1") (pinfunction "C_1") (pintype "passive"))
      (node (ref "D3") (pin "2") (pinfunction "A_2") (pintype "passive"))
      (node (ref "D4") (pin "1") (pinfunction "C_1") (pintype "passive"))
      (node (ref "D5") (pin "2") (pinfunction "A_2") (pintype "passive"))
      (node (ref "GND") (pin "1") (pinfunction "P$1_1") (pintype "bidirectional"))
      (node (ref "IC1") (pin "15") (pinfunction "DCDC_GND_15") (pintype "passive"))
      (node (ref "IC1") (pin "9") (pinfunction "GND_9") (pintype "passive"))
      (node (ref "IC11") (pin "31") (pinfunction "RESV1_31") (pintype "input"))
      (node (ref "IC11") (pin "33") (pinfunction "DGND_2_33") (pintype "power_in"))
      (node (ref "IC11") (pin "41") (pinfunction "DAISY_IN_41") (pintype "input"))
      (node (ref "IC11") (pin "49") (pinfunction "DGND_3_49") (pintype "power_in"))
      (node (ref "IC11") (pin "51") (pinfunction "DGND_51") (pintype "power_in"))
      (node (ref "IC12") (pin "2") (pinfunction "GND_2") (pintype "passive"))
      (node (ref "IC13") (pin "1") (pinfunction "GND_1") (pintype "passive"))
      (node (ref "IC2") (pin "9") (pinfunction "GND_9") (pintype "input"))
      (node (ref "IC3") (pin "15") (pinfunction "DCDC_GND_15") (pintype "passive"))
      (node (ref "IC3") (pin "9") (pinfunction "GND_9") (pintype "passive"))
      (node (ref "IC5") (pin "5") (pinfunction "GND_5") (pintype "power_in"))
      (node (ref "IC7") (pin "5") (pinfunction "GND_5") (pintype "power_in"))
      (node (ref "JP5") (pin "2") (pinfunction "2_2") (pintype "passive"))
      (node (ref "JP6") (pin "2") (pinfunction "2_2") (pintype "passive"))
      (node (ref "JP8") (pin "NO") (pinfunction "NO_NO") (pintype "passive"))
      (node (ref "OK1") (pin "2") (pinfunction "C_2") (pintype "passive"))
      (node (ref "OK2") (pin "2") (pinfunction "C_2") (pintype "passive"))
      (node (ref "OK3") (pin "2") (pinfunction "C_2") (pintype "passive"))
      (node (ref "R19") (pin "1") (pinfunction "1_1") (pintype "passive"))
      (node (ref "R27") (pin "2") (pinfunction "2_2") (pintype "passive"))
      (node (ref "R28") (pin "1") (pinfunction "1_1") (pintype "passive"))
      (node (ref "R31") (pin "1") (pinfunction "1_1") (pintype "passive"))
      (node (ref "X2") (pin "1") (pinfunction "1_1") (pintype "passive"))
      (node (ref "X2") (pin "11") (pinfunction "1_11") (pintype "passive"))
      (node (ref "X2") (pin "12") (pinfunction "1_12") (pintype "passive"))
      (node (ref "X2") (pin "2") (pinfunction "1_2") (pintype "passive"))
      (node (ref "X2") (pin "21") (pinfunction "1_21") (pintype "passive"))
      (node (ref "X2") (pin "22") (pinfunction "1_22") (pintype "passive"))
      (node (ref "X2") (pin "27") (pinfunction "1_27") (pintype "passive"))
      (node (ref "X2") (pin "28") (pinfunction "1_28") (pintype "passive"))
      (node (ref "X3") (pin "1") (pinfunction "1_1") (pintype "passive"))
      (node (ref "X3") (pin "27") (pinfunction "1_27") (pintype "passive"))
      (node (ref "X3") (pin "28") (pinfunction "1_28") (pintype "passive"))
    )
    (net (code "25") (name "HI_CLAMP") (class "Default")
      (node (ref "IC4") (pin "10") (pinfunction "+IN_10") (pintype "input"))
      (node (ref "IC4") (pin "5") (pinfunction "+IN_5") (pintype "input"))
      (node (ref "R26") (pin "2") (pinfunction "2_2") (pintype "passive"))
      (node (ref "R27") (pin "1") (pinfunction "1_1") (pintype "passive"))
    )
    (net (code "26") (name "IN1N") (class "Default")
      (node (ref "IC1") (pin "10") (pinfunction "OUTN_10") (pintype "output"))
      (node (ref "IC11") (pin "15") (pinfunction "IN1N_15") (pintype "input"))
    )
    (net (code "27") (name "IN1P") (class "Default")
      (node (ref "IC1") (pin "11") (pinfunction "OUTP_11") (pintype "output"))
      (node (ref "IC11") (pin "16") (pinfunction "IN1P_16") (pintype "input"))
    )
    (net (code "28") (name "IN2N") (class "Default")
      (node (ref "IC11") (pin "13") (pinfunction "IN2N_13") (pintype "input"))
      (node (ref "IC3") (pin "10") (pinfunction "OUTN_10") (pintype "output"))
    )
    (net (code "29") (name "IN2P") (class "Default")
      (node (ref "IC11") (pin "14") (pinfunction "IN2P_14") (pintype "input"))
      (node (ref "IC3") (pin "11") (pinfunction "OUTP_11") (pintype "output"))
    )
    (net (code "30") (name "IN3N") (class "Default")
      (node (ref "D2") (pin "2") (pinfunction "A_2") (pintype "passive"))
      (node (ref "D3") (pin "1") (pinfunction "C_1") (pintype "passive"))
      (node (ref "IC11") (pin "11") (pinfunction "IN3N_11") (pintype "input"))
      (node (ref "JP3") (pin "1") (pinfunction "1_1") (pintype "passive"))
      (node (ref "JP5") (pin "1") (pinfunction "1_1") (pintype "passive"))
      (node (ref "R15") (pin "1") (pinfunction "1_1") (pintype "passive"))
      (node (ref "R19") (pin "2") (pinfunction "2_2") (pintype "passive"))
      (node (ref "R25") (pin "1") (pinfunction "1_1") (pintype "passive"))
      (node (ref "X1") (pin "6") (pinfunction "1_6") (pintype "passive"))
    )
    (net (code "31") (name "IN3P") (class "Default")
      (node (ref "D1") (pin "3") (pinfunction "AC_3") (pintype "passive"))
      (node (ref "IC11") (pin "12") (pinfunction "IN3P_12") (pintype "input"))
      (node (ref "IC4") (pin "2") (pinfunction "-IN_2") (pintype "input"))
      (node (ref "IC4") (pin "6") (pinfunction "-IN_6") (pintype "input"))
      (node (ref "IC5") (pin "10") (pinfunction "D_10") (pintype "bidirectional"))
      (node (ref "IC5") (pin "15") (pinfunction "D_15") (pintype "bidirectional"))
      (node (ref "IC5") (pin "2") (pinfunction "D_2") (pintype "bidirectional"))
      (node (ref "IC5") (pin "7") (pinfunction "D_7") (pintype "bidirectional"))
    )
    (net (code "32") (name "IN4N") (class "Default")
      (node (ref "IC11") (pin "9") (pinfunction "IN4N_9") (pintype "input"))
      (node (ref "JP1") (pin "1") (pinfunction "1_1") (pintype "passive"))
      (node (ref "R35") (pin "1S") (pinfunction "1S_1S") (pintype "passive"))
      (node (ref "R39") (pin "1") (pinfunction "1_1") (pintype "passive"))
    )
    (net (code "33") (name "IN4P") (class "Default")
      (node (ref "D10") (pin "3") (pinfunction "AC_3") (pintype "passive"))
      (node (ref "IC11") (pin "10") (pinfunction "IN4P_10") (pintype "input"))
      (node (ref "IC4") (pin "13") (pinfunction "-IN_13") (pintype "input"))
      (node (ref "IC4") (pin "9") (pinfunction "-IN_9") (pintype "input"))
      (node (ref "IC7") (pin "11") (pinfunction "S_11") (pintype "bidirectional"))
      (node (ref "IC7") (pin "15") (pinfunction "D_15") (pintype "bidirectional"))
      (node (ref "IC7") (pin "3") (pinfunction "S_3") (pintype "bidirectional"))
      (node (ref "IC7") (pin "7") (pinfunction "D_7") (pintype "bidirectional"))
    )
    (net (code "34") (name "ISEL#3") (class "Default")
      (node (ref "IC5") (pin "9") (pinfunction "IN_9") (pintype "input"))
      (node (ref "R14") (pin "2") (pinfunction "2_2") (pintype "passive"))
      (node (ref "X3") (pin "15") (pinfunction "1_15") (pintype "passive"))
    )
    (net (code "35") (name "ISEL10A_R4_OUT") (class "Default")
      (node (ref "IC2") (pin "11") (pinfunction "8C_11") (pintype "output"))
      (node (ref "ISEL10A_2") (pin "A1") (pinfunction "R_A1") (pintype "passive"))
    )
    (net (code "36") (name "ISEL10A_S4_OUT") (class "Default")
      (node (ref "IC2") (pin "12") (pinfunction "7C_12") (pintype "output"))
      (node (ref "ISEL10A_2") (pin "A2") (pinfunction "S_A2") (pintype "passive"))
    )
    (net (code "37") (name "ISEL10_R#4") (class "Default")
      (node (ref "IC2") (pin "8") (pinfunction "8B_8") (pintype "input"))
      (node (ref "X3") (pin "22") (pinfunction "1_22") (pintype "passive"))
    )
    (net (code "38") (name "ISEL10_S#4") (class "Default")
      (node (ref "IC2") (pin "7") (pinfunction "7B_7") (pintype "input"))
      (node (ref "X3") (pin "20") (pinfunction "1_20") (pintype "passive"))
    )
    (net (code "39") (name "ISEL_LOW#4") (class "Default")
      (node (ref "IC7") (pin "16") (pinfunction "IN_16") (pintype "input"))
      (node (ref "X3") (pin "23") (pinfunction "1_23") (pintype "passive"))
    )
    (net (code "40") (name "ISEL_MID#4") (class "Default")
      (node (ref "IC7") (pin "9") (pinfunction "IN_9") (pintype "input"))
      (node (ref "Q3") (pin "1") (pinfunction "G_1") (pintype "passive"))
      (node (ref "Q4") (pin "1") (pinfunction "G_1") (pintype "passive"))
      (node (ref "X3") (pin "24") (pinfunction "1_24") (pintype "passive"))
    )
    (net (code "41") (name "ISEL_R#2") (class "Default")
      (node (ref "IC2") (pin "4") (pinfunction "4B_4") (pintype "input"))
      (node (ref "X3") (pin "8") (pinfunction "1_8") (pintype "passive"))
    )
    (net (code "42") (name "ISEL_R#4") (class "Default")
      (node (ref "IC2") (pin "6") (pinfunction "6B_6") (pintype "input"))
      (node (ref "X3") (pin "18") (pinfunction "1_18") (pintype "passive"))
    )
    (net (code "43") (name "ISEL_R2_OUT") (class "Default")
      (node (ref "IC2") (pin "15") (pinfunction "4C_15") (pintype "output"))
      (node (ref "ISEL10A_1") (pin "A1") (pinfunction "R_A1") (pintype "passive"))
    )
    (net (code "44") (name "ISEL_R4_OUT") (class "Default")
      (node (ref "IC2") (pin "13") (pinfunction "6C_13") (pintype "output"))
      (node (ref "ISEL1A_1") (pin "7") (pinfunction "R-_7") (pintype "passive"))
    )
    (net (code "45") (name "ISEL_S#2") (class "Default")
      (node (ref "IC2") (pin "3") (pinfunction "3B_3") (pintype "input"))
      (node (ref "X3") (pin "6") (pinfunction "1_6") (pintype "passive"))
    )
    (net (code "46") (name "ISEL_S#4") (class "Default")
      (node (ref "IC2") (pin "5") (pinfunction "5B_5") (pintype "input"))
      (node (ref "X3") (pin "16") (pinfunction "1_16") (pintype "passive"))
    )
    (net (code "47") (name "ISEL_S2_OUT") (class "Default")
      (node (ref "IC2") (pin "16") (pinfunction "3C_16") (pintype "output"))
      (node (ref "ISEL10A_1") (pin "A2") (pinfunction "S_A2") (pintype "passive"))
    )
    (net (code "48") (name "ISEL_S4_OUT") (class "Default")
      (node (ref "IC2") (pin "14") (pinfunction "5C_14") (pintype "output"))
      (node (ref "ISEL1A_1") (pin "12") (pinfunction "S-_12") (pintype "passive"))
    )
    (net (code "49") (name "LO_CLAMP") (class "Default")
      (node (ref "IC4") (pin "12") (pinfunction "+IN_12") (pintype "input"))
      (node (ref "IC4") (pin "3") (pinfunction "+IN_3") (pintype "input"))
      (node (ref "R28") (pin "2") (pinfunction "2_2") (pintype "passive"))
      (node (ref "R29") (pin "1") (pinfunction "1_1") (pintype "passive"))
    )
    (net (code "50") (name "Net-(C35-Pad2)") (class "Default")
      (node (ref "C35") (pin "2") (pinfunction "2_2") (pintype "passive"))
      (node (ref "R65") (pin "1") (pinfunction "1_1") (pintype "passive"))
    )
    (net (code "51") (name "Net-(D1-A)") (class "Default")
      (node (ref "D1") (pin "1") (pinfunction "A_1") (pintype "passive"))
      (node (ref "IC4") (pin "1") (pinfunction "OUT_1") (pintype "output"))
    )
    (net (code "52") (name "Net-(D1-C)") (class "Default")
      (node (ref "D1") (pin "2") (pinfunction "C_2") (pintype "passive"))
      (node (ref "IC4") (pin "7") (pinfunction "OUT_7") (pintype "output"))
    )
    (net (code "53") (name "Net-(D6-A)") (class "Default")
      (node (ref "D6") (pin "2") (pinfunction "A_2") (pintype "passive"))
      (node (ref "D7") (pin "1") (pinfunction "C_1") (pintype "passive"))
      (node (ref "IC7") (pin "14") (pinfunction "S_14") (pintype "bidirectional"))
      (node (ref "ISEL1A_1") (pin "5") (pinfunction "NO_5") (pintype "passive"))
      (node (ref "ISEL1A_1") (pin "8") (pinfunction "NO_8") (pintype "passive"))
      (node (ref "Q3") (pin "2") (pinfunction "S_2") (pintype "passive"))
      (node (ref "R30") (pin "2") (pinfunction "2_2") (pintype "passive"))
      (node (ref "R33") (pin "2") (pinfunction "2_2") (pintype "passive"))
    )
    (net (code "54") (name "Net-(D6-C)") (class "Default")
      (node (ref "D6") (pin "1") (pinfunction "C_1") (pintype "passive"))
      (node (ref "D7") (pin "2") (pinfunction "A_2") (pintype "passive"))
      (node (ref "D8") (pin "1") (pinfunction "C_1") (pintype "passive"))
      (node (ref "D9") (pin "2") (pinfunction "A_2") (pintype "passive"))
      (node (ref "R34") (pin "2") (pinfunction "2_2") (pintype "passive"))
    )
    (net (code "55") (name "Net-(D10-A)") (class "Default")
      (node (ref "D10") (pin "1") (pinfunction "A_1") (pintype "passive"))
      (node (ref "IC4") (pin "14") (pinfunction "OUT_14") (pintype "output"))
    )
    (net (code "56") (name "Net-(D10-C)") (class "Default")
      (node (ref "D10") (pin "2") (pinfunction "C_2") (pintype "passive"))
      (node (ref "IC4") (pin "8") (pinfunction "OUT_8") (pintype "output"))
    )
    (net (code "57") (name "Net-(F2-Pad2)") (class "Default")
      (node (ref "F2") (pin "2") (pinfunction "2_2") (pintype "passive"))
      (node (ref "R8") (pin "2") (pinfunction "2_2") (pintype "passive"))
    )
    (net (code "58") (name "Net-(F3-P$1)") (class "Default")
      (node (ref "F3") (pin "1") (pinfunction "P$1_1") (pintype "bidirectional"))
      (node (ref "R13") (pin "1") (pinfunction "1_1") (pintype "passive"))
    )
    (net (code "59") (name "Net-(F3-P$2)") (class "Default")
      (node (ref "F3") (pin "2") (pinfunction "P$2_2") (pintype "bidirectional"))
      (node (ref "Q1") (pin "1") (pinfunction "G_1") (pintype "passive"))
      (node (ref "Q2") (pin "3") (pinfunction "S_3") (pintype "passive"))
    )
    (net (code "60") (name "Net-(IC1-DCDC_IN)") (class "Default")
      (node (ref "C3") (pin "1") (pinfunction "1_1") (pintype "passive"))
      (node (ref "IC1") (pin "13") (pinfunction "LDO_OUT_13") (pintype "passive"))
      (node (ref "IC1") (pin "16") (pinfunction "DCDC_IN_16") (pintype "passive"))
    )
    (net (code "61") (name "Net-(IC1-DCDC_OUT)") (class "Default")
      (node (ref "C1") (pin "1") (pinfunction "1_1") (pintype "passive"))
      (node (ref "C2") (pin "1") (pinfunction "1_1") (pintype "passive"))
      (node (ref "C4") (pin "2") (pinfunction "2_2") (pintype "passive"))
      (node (ref "IC1") (pin "1") (pinfunction "DCDC_OUT_1") (pintype "passive"))
      (node (ref "IC1") (pin "3") (pinfunction "HLDO_IN_3") (pintype "passive"))
    )
    (net (code "62") (name "Net-(IC1-HLDO_OUT)") (class "Default")
      (node (ref "C7") (pin "1") (pinfunction "1_1") (pintype "passive"))
      (node (ref "C8") (pin "1") (pinfunction "1_1") (pintype "passive"))
      (node (ref "IC1") (pin "5") (pinfunction "HLDO_OUT_5") (pintype "passive"))
    )
    (net (code "63") (name "Net-(IC1-INP)") (class "Default")
      (node (ref "IC1") (pin "6") (pinfunction "INP_6") (pintype "input"))
      (node (ref "OK1") (pin "4") (pinfunction "S1_4") (pintype "passive"))
      (node (ref "R5") (pin "1") (pinfunction "1_1") (pintype "passive"))
      (node (ref "R7") (pin "2") (pinfunction "2_2") (pintype "passive"))
    )
    (net (code "64") (name "Net-(IC2-COM)") (class "Default")
      (node (ref "IC2") (pin "10") (pinfunction "COM_10") (pintype "passive"))
      (node (ref "ZD1") (pin "C") (pinfunction "C_C") (pintype "passive"))
    )
    (net (code "65") (name "Net-(IC3-DCDC_HGND)") (class "Default")
      (node (ref "C10") (pin "2") (pinfunction "2_2") (pintype "passive"))
      (node (ref "C12") (pin "1") (pinfunction "1_1") (pintype "passive"))
      (node (ref "C15") (pin "2") (pinfunction "2_2") (pintype "passive"))
      (node (ref "C16") (pin "2") (pinfunction "2_2") (pintype "passive"))
      (node (ref "C9") (pin "2") (pinfunction "2_2") (pintype "passive"))
      (node (ref "IC3") (pin "2") (pinfunction "DCDC_HGND_2") (pintype "passive"))
      (node (ref "IC3") (pin "8") (pinfunction "HGND_8") (pintype "passive"))
      (node (ref "L2") (pin "2") (pinfunction "2_2") (pintype "passive"))
      (node (ref "R12") (pin "2") (pinfunction "2_2") (pintype "passive"))
    )
    (net (code "66") (name "Net-(IC3-DCDC_IN)") (class "Default")
      (node (ref "C11") (pin "1") (pinfunction "1_1") (pintype "passive"))
      (node (ref "IC3") (pin "13") (pinfunction "LDO_OUT_13") (pintype "passive"))
      (node (ref "IC3") (pin "16") (pinfunction "DCDC_IN_16") (pintype "passive"))
    )
    (net (code "67") (name "Net-(IC3-DCDC_OUT)") (class "Default")
      (node (ref "C10") (pin "1") (pinfunction "1_1") (pintype "passive"))
      (node (ref "C12") (pin "2") (pinfunction "2_2") (pintype "passive"))
      (node (ref "C9") (pin "1") (pinfunction "1_1") (pintype "passive"))
      (node (ref "IC3") (pin "1") (pinfunction "DCDC_OUT_1") (pintype "passive"))
      (node (ref "IC3") (pin "3") (pinfunction "HLDO_IN_3") (pintype "passive"))
    )
    (net (code "68") (name "Net-(IC3-HLDO_OUT)") (class "Default")
      (node (ref "C15") (pin "1") (pinfunction "1_1") (pintype "passive"))
      (node (ref "C16") (pin "1") (pinfunction "1_1") (pintype "passive"))
      (node (ref "IC3") (pin "5") (pinfunction "HLDO_OUT_5") (pintype "passive"))
    )
    (net (code "69") (name "Net-(IC3-INN)") (class "Default")
      (node (ref "C17") (pin "2") (pinfunction "2_2") (pintype "passive"))
      (node (ref "IC3") (pin "7") (pinfunction "INN_7") (pintype "input"))
      (node (ref "R12") (pin "1") (pinfunction "1_1") (pintype "passive"))
    )
    (net (code "70") (name "Net-(IC3-INP)") (class "Default")
      (node (ref "C17") (pin "1") (pinfunction "1_1") (pintype "passive"))
      (node (ref "IC3") (pin "6") (pinfunction "INP_6") (pintype "input"))
      (node (ref "R10") (pin "1") (pinfunction "1_1") (pintype "passive"))
    )
    (net (code "71") (name "Net-(IC5A-S)") (class "Default")
      (node (ref "IC5") (pin "3") (pinfunction "S_3") (pintype "bidirectional"))
      (node (ref "R22") (pin "1") (pinfunction "1_1") (pintype "passive"))
      (node (ref "R23") (pin "2") (pinfunction "2_2") (pintype "passive"))
    )
    (net (code "72") (name "Net-(IC5B-S)") (class "Default")
      (node (ref "IC5") (pin "14") (pinfunction "S_14") (pintype "bidirectional"))
      (node (ref "R24") (pin "1") (pinfunction "1_1") (pintype "passive"))
      (node (ref "R25") (pin "2") (pinfunction "2_2") (pintype "passive"))
    )
    (net (code "73") (name "Net-(IC5C-S)") (class "Default")
      (node (ref "IC5") (pin "11") (pinfunction "S_11") (pintype "bidirectional"))
      (node (ref "Q2") (pin "2") (pinfunction "D_2") (pintype "passive"))
      (node (ref "Q2") (pin "4") (pinfunction "D_4") (pintype "passive"))
      (node (ref "R15") (pin "2") (pinfunction "2_2") (pintype "passive"))
    )
    (net (code "74") (name "Net-(IC5D-S)") (class "Default")
      (node (ref "IC5") (pin "6") (pinfunction "S_6") (pintype "bidirectional"))
      (node (ref "OK3") (pin "4") (pinfunction "S1_4") (pintype "passive"))
    )
    (net (code "75") (name "Net-(IC6A-+IN)") (class "Default")
      (node (ref "IC6") (pin "3") (pinfunction "+IN_3") (pintype "input"))
      (node (ref "R33") (pin "1") (pinfunction "1_1") (pintype "passive"))
    )
    (net (code "76") (name "Net-(IC6A--IN)") (class "Default")
      (node (ref "IC6") (pin "1") (pinfunction "OUT_1") (pintype "output"))
      (node (ref "IC6") (pin "4") (pinfunction "-IN_4") (pintype "input"))
      (node (ref "R34") (pin "1") (pinfunction "1_1") (pintype "passive"))
    )
    (net (code "77") (name "Net-(IC7A-D)") (class "Default")
      (node (ref "IC7") (pin "2") (pinfunction "D_2") (pintype "bidirectional"))
      (node (ref "R38") (pin "1") (pinfunction "1_1") (pintype "passive"))
      (node (ref "R39") (pin "2") (pinfunction "2_2") (pintype "passive"))
    )
    (net (code "78") (name "Net-(IC7C-D)") (class "Default")
      (node (ref "IC7") (pin "10") (pinfunction "D_10") (pintype "bidirectional"))
      (node (ref "R32") (pin "2S") (pinfunction "2S_2S") (pintype "passive"))
    )
    (net (code "79") (name "Net-(IC7D-S)") (class "Default")
      (node (ref "IC7") (pin "6") (pinfunction "S_6") (pintype "bidirectional"))
      (node (ref "R36") (pin "1") (pinfunction "1_1") (pintype "passive"))
    )
    (net (code "80") (name "Net-(IC11-AVDD)") (class "Default")
      (node (ref "C54") (pin "2") (pinfunction "2_2") (pintype "passive"))
      (node (ref "C55") (pin "1") (pinfunction "1_1") (pintype "passive"))
      (node (ref "C56") (pin "1") (pinfunction "1_1") (pintype "passive"))
      (node (ref "C57") (pin "1") (pinfunction "1_1") (pintype "passive"))
      (node (ref "C58") (pin "1") (pinfunction "1_1") (pintype "passive"))
      (node (ref "C59") (pin "2") (pinfunction "2_2") (pintype "passive"))
      (node (ref "IC11") (pin "19") (pinfunction "AVDD_2_19") (pintype "power_in"))
      (node (ref "IC11") (pin "21") (pinfunction "AVDD_3_21") (pintype "power_in"))
      (node (ref "IC11") (pin "22") (pinfunction "AVDD_4_22") (pintype "power_in"))
      (node (ref "IC11") (pin "54") (pinfunction "AVDD1_54") (pintype "power_in"))
      (node (ref "IC11") (pin "56") (pinfunction "AVDD_5_56") (pintype "power_in"))
      (node (ref "IC11") (pin "59") (pinfunction "AVDD_59") (pintype "power_in"))
      (node (ref "R53") (pin "2") (pinfunction "2_2") (pintype "passive"))
    )
    (net (code "81") (name "Net-(IC11-CLK)") (class "Default")
      (node (ref "IC11") (pin "37") (pinfunction "CLK_37") (pintype "input"))
      (node (ref "JP9") (pin "2") (pinfunction "2_2") (pintype "passive"))
    )
    (net (code "82") (name "Net-(IC11-CLKSEL)") (class "Default")
      (node (ref "IC11") (pin "52") (pinfunction "CLKSEL_52") (pintype "input"))
      (node (ref "R52") (pin "1") (pinfunction "1_1") (pintype "passive"))
    )
    (net (code "83") (name "Net-(IC11-VCAP1)") (class "Default")
      (node (ref "C33") (pin "2") (pinfunction "2_2") (pintype "passive"))
      (node (ref "IC11") (pin "28") (pinfunction "VCAP1_28") (pintype "passive"))
    )
    (net (code "84") (name "Net-(IC11-VCAP2)") (class "Default")
      (node (ref "C27") (pin "2") (pinfunction "2_2") (pintype "passive"))
      (node (ref "IC11") (pin "30") (pinfunction "VCAP2_30") (pintype "passive"))
    )
    (net (code "85") (name "Net-(IC11-VCAP3)") (class "Default")
      (node (ref "C25") (pin "2") (pinfunction "2_2") (pintype "passive"))
      (node (ref "C26") (pin "1") (pinfunction "1_1") (pintype "passive"))
      (node (ref "IC11") (pin "55") (pinfunction "VCAP3_55") (pintype "passive"))
    )
    (net (code "86") (name "Net-(IC11-VCAP4)") (class "Default")
      (node (ref "C23") (pin "2") (pinfunction "2_2") (pintype "passive"))
      (node (ref "IC11") (pin "26") (pinfunction "VCAP4_26") (pintype "output"))
    )
    (net (code "87") (name "Net-(IC11-VREFP)") (class "Default")
      (node (ref "C28") (pin "1") (pinfunction "1_1") (pintype "passive"))
      (node (ref "C34") (pin "1") (pinfunction "1_1") (pintype "passive"))
      (node (ref "C35") (pin "1") (pinfunction "1_1") (pintype "passive"))
      (node (ref "IC11") (pin "24") (pinfunction "VREFP_24") (pintype "bidirectional"))
      (node (ref "IC8") (pin "6") (pinfunction "VOUT_S_6") (pintype "output"))
      (node (ref "IC8") (pin "7") (pinfunction "VOUT_F_7") (pintype "output"))
    )
    (net (code "88") (name "Net-(IC11-~{PWDN})") (class "Default")
      (node (ref "IC11") (pin "35") (pinfunction "~{PWDN}_35") (pintype "input"))
      (node (ref "R51") (pin "1") (pinfunction "1_1") (pintype "passive"))
    )
    (net (code "89") (name "Net-(IC12-EN)") (class "Default")
      (node (ref "C46") (pin "1") (pinfunction "1_1") (pintype "passive"))
      (node (ref "IC12") (pin "1") (pinfunction "IN_1") (pintype "input"))
      (node (ref "IC12") (pin "3") (pinfunction "EN_3") (pintype "input"))
      (node (ref "L4") (pin "P$1") (pinfunction "1_P$1") (pintype "passive"))
    )
    (net (code "90") (name "Net-(IC13-EN)") (class "Default")
      (node (ref "C47") (pin "1") (pinfunction "1_1") (pintype "passive"))
      (node (ref "IC13") (pin "2") (pinfunction "IN_2") (pintype "input"))
      (node (ref "IC13") (pin "3") (pinfunction "EN_3") (pintype "input"))
      (node (ref "L5") (pin "P$1") (pinfunction "1_P$1") (pintype "passive"))
    )
    (net (code "91") (name "Net-(ISEL1A_1B-COM)") (class "Default")
      (node (ref "F5") (pin "1") (pinfunction "1_1") (pintype "passive"))
      (node (ref "ISEL1A_1") (pin "4") (pinfunction "COM_4") (pintype "passive"))
      (node (ref "ISEL1A_1") (pin "9") (pinfunction "COM_9") (pintype "passive"))
    )
    (net (code "92") (name "Net-(ISEL10A_1B-COM)") (class "Default")
      (node (ref "F1") (pin "1") (pinfunction "1_1") (pintype "passive"))
      (node (ref "F2") (pin "1") (pinfunction "1_1") (pintype "passive"))
      (node (ref "ISEL10A_1") (pin "11") (pinfunction "COM_11") (pintype "passive"))
    )
    (net (code "93") (name "Net-(ISEL10A_1B-NC)") (class "Default")
      (node (ref "ISEL10A_1") (pin "12") (pinfunction "NC_12") (pintype "passive"))
      (node (ref "R11") (pin "2") (pinfunction "2_2") (pintype "passive"))
      (node (ref "R8") (pin "1") (pinfunction "1_1") (pintype "passive"))
      (node (ref "R8") (pin "1S") (pinfunction "1S_1S") (pintype "passive"))
    )
    (net (code "94") (name "Net-(ISEL10A_1C-COM)") (class "Default")
      (node (ref "ISEL10A_1") (pin "21") (pinfunction "COM_21") (pintype "passive"))
      (node (ref "L2") (pin "4") (pinfunction "4_4") (pintype "passive"))
    )
    (net (code "95") (name "Net-(ISEL10A_1C-NC)") (class "Default")
      (node (ref "ISEL10A_1") (pin "22") (pinfunction "NC_22") (pintype "passive"))
      (node (ref "R11") (pin "2S") (pinfunction "2S_2S") (pintype "passive"))
    )
    (net (code "96") (name "Net-(ISEL10A_1C-NO)") (class "Default")
      (node (ref "ISEL10A_1") (pin "24") (pinfunction "NO_24") (pintype "passive"))
      (node (ref "R8") (pin "2S") (pinfunction "2S_2S") (pintype "passive"))
    )
    (net (code "97") (name "Net-(ISEL10A_2B-COM)") (class "Default")
      (node (ref "F4") (pin "1") (pinfunction "1_1") (pintype "passive"))
      (node (ref "ISEL10A_2") (pin "11") (pinfunction "COM_11") (pintype "passive"))
      (node (ref "ISEL10A_2") (pin "21") (pinfunction "COM_21") (pintype "passive"))
    )
    (net (code "98") (name "Net-(ISEL10A_2B-NC)") (class "Default")
      (node (ref "ISEL10A_2") (pin "12") (pinfunction "NC_12") (pintype "passive"))
      (node (ref "ISEL10A_2") (pin "22") (pinfunction "NC_22") (pintype "passive"))
      (node (ref "R35") (pin "2") (pinfunction "2_2") (pintype "passive"))
    )
    (net (code "99") (name "Net-(JP8-PadCOM)") (class "Default")
      (node (ref "JP8") (pin "COM") (pinfunction "COM_COM") (pintype "passive"))
      (node (ref "R52") (pin "2") (pinfunction "2_2") (pintype "passive"))
    )
    (net (code "100") (name "Net-(L1-1)") (class "Default")
      (node (ref "L1") (pin "P$1") (pinfunction "1_P$1") (pintype "passive"))
      (node (ref "R1") (pin "2") (pinfunction "2_2") (pintype "passive"))
    )
    (net (code "101") (name "Net-(L2-Pad1)") (class "Default")
      (node (ref "L2") (pin "1") (pinfunction "1_1") (pintype "passive"))
      (node (ref "R11") (pin "1S") (pinfunction "1S_1S") (pintype "passive"))
    )
    (net (code "102") (name "Net-(L2-Pad3)") (class "Default")
      (node (ref "L2") (pin "3") (pinfunction "3_3") (pintype "passive"))
      (node (ref "R10") (pin "2") (pinfunction "2_2") (pintype "passive"))
    )
    (net (code "103") (name "Net-(L3-2)") (class "Default")
      (node (ref "L3") (pin "P$2") (pinfunction "2_P$2") (pintype "passive"))
      (node (ref "X1") (pin "5") (pinfunction "1_5") (pintype "passive"))
    )
    (net (code "104") (name "Net-(OK1-A)") (class "Default")
      (node (ref "OK1") (pin "1") (pinfunction "A_1") (pintype "passive"))
      (node (ref "R2") (pin "1") (pinfunction "1_1") (pintype "passive"))
    )
    (net (code "105") (name "Net-(OK1-S2)") (class "Default")
      (node (ref "OK1") (pin "3") (pinfunction "S2_3") (pintype "passive"))
      (node (ref "R6") (pin "2") (pinfunction "2_2") (pintype "passive"))
    )
    (net (code "106") (name "Net-(OK2-A)") (class "Default")
      (node (ref "OK2") (pin "1") (pinfunction "A_1") (pintype "passive"))
      (node (ref "R14") (pin "1") (pinfunction "1_1") (pintype "passive"))
    )
    (net (code "107") (name "Net-(OK3-A)") (class "Default")
      (node (ref "OK3") (pin "1") (pinfunction "A_1") (pintype "passive"))
      (node (ref "R16") (pin "2") (pinfunction "2_2") (pintype "passive"))
    )
    (net (code "108") (name "Net-(OK3-S2)") (class "Default")
      (node (ref "OK3") (pin "3") (pinfunction "S2_3") (pintype "passive"))
      (node (ref "R18") (pin "1") (pinfunction "1_1") (pintype "passive"))
    )
    (net (code "109") (name "Net-(Q1-S)") (class "Default")
      (node (ref "Q1") (pin "3") (pinfunction "S_3") (pintype "passive"))
      (node (ref "Q2") (pin "1") (pinfunction "G_1") (pintype "passive"))
      (node (ref "R13") (pin "2") (pinfunction "2_2") (pintype "passive"))
    )
    (net (code "110") (name "Net-(Q3-D)") (class "Default")
      (node (ref "Q3") (pin "3") (pinfunction "D_3") (pintype "passive"))
      (node (ref "Q4") (pin "3") (pinfunction "D_3") (pintype "passive"))
    )
    (net (code "111") (name "Net-(Q4-S)") (class "Default")
      (node (ref "Q4") (pin "2") (pinfunction "S_2") (pintype "passive"))
      (node (ref "R30") (pin "1") (pinfunction "1_1") (pintype "passive"))
      (node (ref "R32") (pin "2") (pinfunction "2_2") (pintype "passive"))
    )
    (net (code "112") (name "Net-(R1-Pad1)") (class "Default")
      (node (ref "R1") (pin "1") (pinfunction "1_1") (pintype "passive"))
      (node (ref "R3") (pin "2") (pinfunction "2_2") (pintype "passive"))
    )
    (net (code "113") (name "Net-(R3-Pad1)") (class "Default")
      (node (ref "R3") (pin "1") (pinfunction "1_1") (pintype "passive"))
      (node (ref "R5") (pin "2") (pinfunction "2_2") (pintype "passive"))
    )
    (net (code "114") (name "Net-(R17-Pad1)") (class "Default")
      (node (ref "R17") (pin "1") (pinfunction "1_1") (pintype "passive"))
      (node (ref "R18") (pin "2") (pinfunction "2_2") (pintype "passive"))
    )
    (net (code "115") (name "Net-(R20-Pad1)") (class "Default")
      (node (ref "R20") (pin "1") (pinfunction "1_1") (pintype "passive"))
      (node (ref "R21") (pin "2") (pinfunction "2_2") (pintype "passive"))
    )
    (net (code "116") (name "Net-(R21-Pad1)") (class "Default")
      (node (ref "R21") (pin "1") (pinfunction "1_1") (pintype "passive"))
      (node (ref "R22") (pin "2") (pinfunction "2_2") (pintype "passive"))
    )
    (net (code "117") (name "Net-(R23-Pad1)") (class "Default")
      (node (ref "R23") (pin "1") (pinfunction "1_1") (pintype "passive"))
      (node (ref "R24") (pin "2") (pinfunction "2_2") (pintype "passive"))
    )
    (net (code "118") (name "Net-(R32-Pad1)") (class "Default")
      (node (ref "R32") (pin "1") (pinfunction "1_1") (pintype "passive"))
      (node (ref "R32") (pin "1S") (pinfunction "1S_1S") (pintype "passive"))
      (node (ref "R35") (pin "2S") (pinfunction "2S_2S") (pintype "passive"))
    )
    (net (code "119") (name "Net-(R37-Pad1)") (class "Default")
      (node (ref "R37") (pin "1") (pinfunction "1_1") (pintype "passive"))
      (node (ref "R38") (pin "2") (pinfunction "2_2") (pintype "passive"))
    )
    (net (code "120") (name "Net-(X1C-1)") (class "Default")
      (node (ref "F1") (pin "2") (pinfunction "2_2") (pintype "passive"))
      (node (ref "X1") (pin "3") (pinfunction "1_3") (pintype "passive"))
    )
    (net (code "121") (name "Net-(X1D-1)") (class "Default")
      (node (ref "R11") (pin "1") (pinfunction "1_1") (pintype "passive"))
      (node (ref "X1") (pin "4") (pinfunction "1_4") (pintype "passive"))
    )
    (net (code "122") (name "Net-(X2P-1)") (class "Default")
      (node (ref "JP1") (pin "2") (pinfunction "2_2") (pintype "passive"))
      (node (ref "X2") (pin "23") (pinfunction "1_23") (pintype "passive"))
    )
    (net (code "123") (name "Net-(X2Q-1)") (class "Default")
      (node (ref "JP2") (pin "1") (pinfunction "1_1") (pintype "passive"))
      (node (ref "X2") (pin "24") (pinfunction "1_24") (pintype "passive"))
    )
    (net (code "124") (name "Net-(X2R-1)") (class "Default")
      (node (ref "JP3") (pin "2") (pinfunction "2_2") (pintype "passive"))
      (node (ref "X2") (pin "25") (pinfunction "1_25") (pintype "passive"))
    )
    (net (code "125") (name "Net-(X2S-1)") (class "Default")
      (node (ref "JP4") (pin "1") (pinfunction "1_1") (pintype "passive"))
      (node (ref "X2") (pin "26") (pinfunction "1_26") (pintype "passive"))
    )
    (net (code "126") (name "USEL#1") (class "Default")
      (node (ref "R2") (pin "2") (pinfunction "2_2") (pintype "passive"))
      (node (ref "X3") (pin "5") (pinfunction "1_5") (pintype "passive"))
    )
    (net (code "127") (name "USEL1#3") (class "Default")
      (node (ref "IC5") (pin "8") (pinfunction "IN_8") (pintype "input"))
      (node (ref "R16") (pin "1") (pinfunction "1_1") (pintype "passive"))
      (node (ref "X3") (pin "11") (pinfunction "1_11") (pintype "passive"))
    )
    (net (code "128") (name "USEL1#4") (class "Default")
      (node (ref "IC7") (pin "8") (pinfunction "IN_8") (pintype "input"))
      (node (ref "X3") (pin "12") (pinfunction "1_12") (pintype "passive"))
    )
    (net (code "129") (name "USEL5#4") (class "Default")
      (node (ref "IC7") (pin "1") (pinfunction "IN_1") (pintype "input"))
      (node (ref "X3") (pin "14") (pinfunction "1_14") (pintype "passive"))
    )
    (net (code "130") (name "USEL20#3") (class "Default")
      (node (ref "IC5") (pin "1") (pinfunction "IN_1") (pintype "input"))
      (node (ref "X3") (pin "13") (pinfunction "1_13") (pintype "passive"))
    )
    (net (code "131") (name "USEL100#3") (class "Default")
      (node (ref "IC5") (pin "16") (pinfunction "IN_16") (pintype "input"))
      (node (ref "X3") (pin "9") (pinfunction "1_9") (pintype "passive"))
    )
    (net (code "132") (name "unconnected-(IC2-1B-Pad1)") (class "Default")
      (node (ref "IC2") (pin "1") (pinfunction "1B_1") (pintype "input"))
    )
    (net (code "133") (name "unconnected-(IC2-1C-Pad18)") (class "Default")
      (node (ref "IC2") (pin "18") (pinfunction "1C_18") (pintype "output"))
    )
    (net (code "134") (name "unconnected-(IC2-2B-Pad2)") (class "Default")
      (node (ref "IC2") (pin "2") (pinfunction "2B_2") (pintype "input"))
    )
    (net (code "135") (name "unconnected-(IC2-2C-Pad17)") (class "Default")
      (node (ref "IC2") (pin "17") (pinfunction "2C_17") (pintype "output"))
    )
    (net (code "136") (name "unconnected-(IC11-GPIO1-Pad42)") (class "Default")
      (node (ref "IC11") (pin "42") (pinfunction "GPIO1_42") (pintype "bidirectional"))
    )
    (net (code "137") (name "unconnected-(IC11-GPIO2-Pad44)") (class "Default")
      (node (ref "IC11") (pin "44") (pinfunction "GPIO2_44") (pintype "bidirectional"))
    )
    (net (code "138") (name "unconnected-(IC11-GPIO3-Pad45)") (class "Default")
      (node (ref "IC11") (pin "45") (pinfunction "GPIO3_45") (pintype "bidirectional"))
    )
    (net (code "139") (name "unconnected-(IC11-GPIO4-Pad46)") (class "Default")
      (node (ref "IC11") (pin "46") (pinfunction "GPIO4_46") (pintype "bidirectional"))
    )
    (net (code "140") (name "unconnected-(IC11-IN5N(NC)-Pad7)") (class "Default")
      (node (ref "IC11") (pin "7") (pinfunction "IN5N(NC)_7") (pintype "input"))
    )
    (net (code "141") (name "unconnected-(IC11-IN5P(NC)-Pad8)") (class "Default")
      (node (ref "IC11") (pin "8") (pinfunction "IN5P(NC)_8") (pintype "input"))
    )
    (net (code "142") (name "unconnected-(IC11-IN6N(NC)-Pad5)") (class "Default")
      (node (ref "IC11") (pin "5") (pinfunction "IN6N(NC)_5") (pintype "input"))
    )
    (net (code "143") (name "unconnected-(IC11-IN6P(NC)-Pad6)") (class "Default")
      (node (ref "IC11") (pin "6") (pinfunction "IN6P(NC)_6") (pintype "input"))
    )
    (net (code "144") (name "unconnected-(IC11-IN7N(NC)-Pad3)") (class "Default")
      (node (ref "IC11") (pin "3") (pinfunction "IN7N(NC)_3") (pintype "input"))
    )
    (net (code "145") (name "unconnected-(IC11-IN7P(NC)-Pad4)") (class "Default")
      (node (ref "IC11") (pin "4") (pinfunction "IN7P(NC)_4") (pintype "input"))
    )
    (net (code "146") (name "unconnected-(IC11-IN8N(NC)-Pad1)") (class "Default")
      (node (ref "IC11") (pin "1") (pinfunction "IN8N(NC)_1") (pintype "input"))
    )
    (net (code "147") (name "unconnected-(IC11-IN8P(NC)-Pad2)") (class "Default")
      (node (ref "IC11") (pin "2") (pinfunction "IN8P(NC)_2") (pintype "input"))
    )
    (net (code "148") (name "unconnected-(IC11-OPAMPN-Pad61)") (class "Default")
      (node (ref "IC11") (pin "61") (pinfunction "OPAMPN_61") (pintype "input"))
    )
    (net (code "149") (name "unconnected-(IC11-OPAMPOUT-Pad63)") (class "Default")
      (node (ref "IC11") (pin "63") (pinfunction "OPAMPOUT_63") (pintype "output"))
    )
    (net (code "150") (name "unconnected-(IC11-OPAMPP-Pad60)") (class "Default")
      (node (ref "IC11") (pin "60") (pinfunction "OPAMPP_60") (pintype "input"))
    )
    (net (code "151") (name "unconnected-(IC11-TESTN-Pad18)") (class "Default")
      (node (ref "IC11") (pin "18") (pinfunction "TESTN_18") (pintype "bidirectional"))
    )
    (net (code "152") (name "unconnected-(IC11-TESTP-Pad17)") (class "Default")
      (node (ref "IC11") (pin "17") (pinfunction "TESTP_17") (pintype "bidirectional"))
    )
    (net (code "153") (name "unconnected-(IC12-NR-Pad4)") (class "Default")
      (node (ref "IC12") (pin "4") (pinfunction "NR_4") (pintype "passive"))
    )
    (net (code "154") (name "unconnected-(IC13-NR-Pad4)") (class "Default")
      (node (ref "IC13") (pin "4") (pinfunction "NR_4") (pintype "passive"))
    )
    (net (code "155") (name "unconnected-(ISEL10A_1B-NO-Pad14)") (class "Default")
      (node (ref "ISEL10A_1") (pin "14") (pinfunction "NO_14") (pintype "passive"))
    )
    (net (code "156") (name "unconnected-(ISEL10A_2B-NO-Pad14)") (class "Default")
      (node (ref "ISEL10A_2") (pin "14") (pinfunction "NO_14") (pintype "passive"))
    )
    (net (code "157") (name "unconnected-(ISEL10A_2C-NO-Pad24)") (class "Default")
      (node (ref "ISEL10A_2") (pin "24") (pinfunction "NO_24") (pintype "passive"))
    )
    (net (code "158") (name "unconnected-(X2I-1-Pad17)") (class "Default")
      (node (ref "X2") (pin "17") (pinfunction "1_17") (pintype "passive"))
    )
    (net (code "159") (name "unconnected-(X2J-1-Pad18)") (class "Default")
      (node (ref "X2") (pin "18") (pinfunction "1_18") (pintype "passive"))
    )
    (net (code "160") (name "unconnected-(X3B-1-Pad10)") (class "Default")
      (node (ref "X3") (pin "10") (pinfunction "1_10") (pintype "passive"))
    )
    (net (code "161") (name "unconnected-(X3I-1-Pad17)") (class "Default")
      (node (ref "X3") (pin "17") (pinfunction "1_17") (pintype "passive"))
    )
    (net (code "162") (name "unconnected-(X3K-1-Pad19)") (class "Default")
      (node (ref "X3") (pin "19") (pinfunction "1_19") (pintype "passive"))
    )
    (net (code "163") (name "unconnected-(X3L-1-Pad2)") (class "Default")
      (node (ref "X3") (pin "2") (pinfunction "1_2") (pintype "passive"))
    )
    (net (code "164") (name "unconnected-(X3N-1-Pad21)") (class "Default")
      (node (ref "X3") (pin "21") (pinfunction "1_21") (pintype "passive"))
    )
    (net (code "165") (name "unconnected-(X3R-1-Pad25)") (class "Default")
      (node (ref "X3") (pin "25") (pinfunction "1_25") (pintype "passive"))
    )
    (net (code "166") (name "unconnected-(X3S-1-Pad26)") (class "Default")
      (node (ref "X3") (pin "26") (pinfunction "1_26") (pintype "passive"))
    )
    (net (code "167") (name "unconnected-(X3Z-1-Pad7)") (class "Default")
      (node (ref "X3") (pin "7") (pinfunction "1_7") (pintype "passive"))
    )
    (net (code "168") (name "~{ADC_CS}") (class "Default")
      (node (ref "IC11") (pin "39") (pinfunction "~{CS}_39") (pintype "input"))
      (node (ref "X2") (pin "5") (pinfunction "1_5") (pintype "passive"))
    )
    (net (code "169") (name "~{ADC_DRDY}") (class "Default")
      (node (ref "IC11") (pin "47") (pinfunction "~{DRDY}_47") (pintype "output"))
      (node (ref "X2") (pin "7") (pinfunction "1_7") (pintype "passive"))
    )
    (net (code "170") (name "~{RESET}") (class "Default")
      (node (ref "IC11") (pin "36") (pinfunction "~{RESET}_36") (pintype "input"))
      (node (ref "X2") (pin "9") (pinfunction "1_9") (pintype "passive"))
    )
  )
)
